# Octoprober.net
KiCad netlist of a schematic drawn in EAGLE
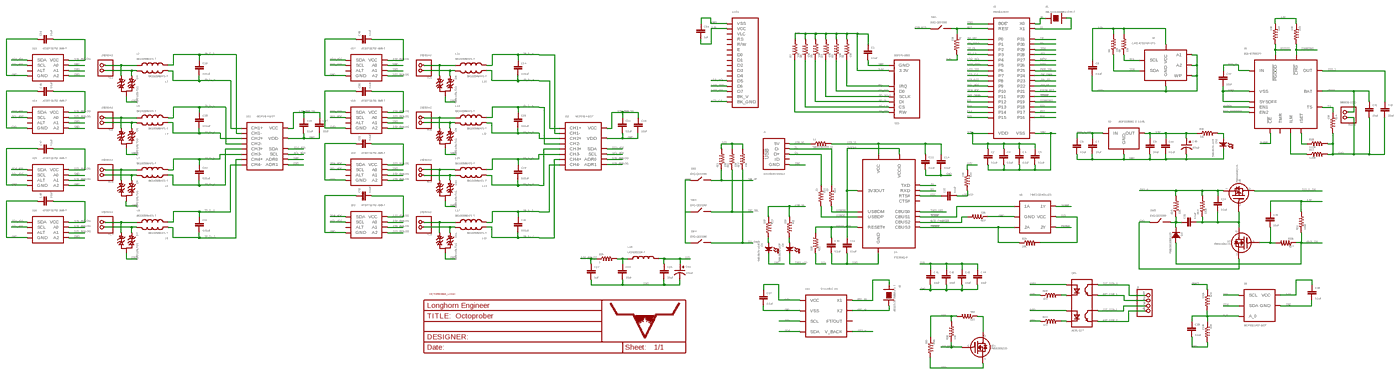
[diagram p0: schematic, sheet 1, overview]
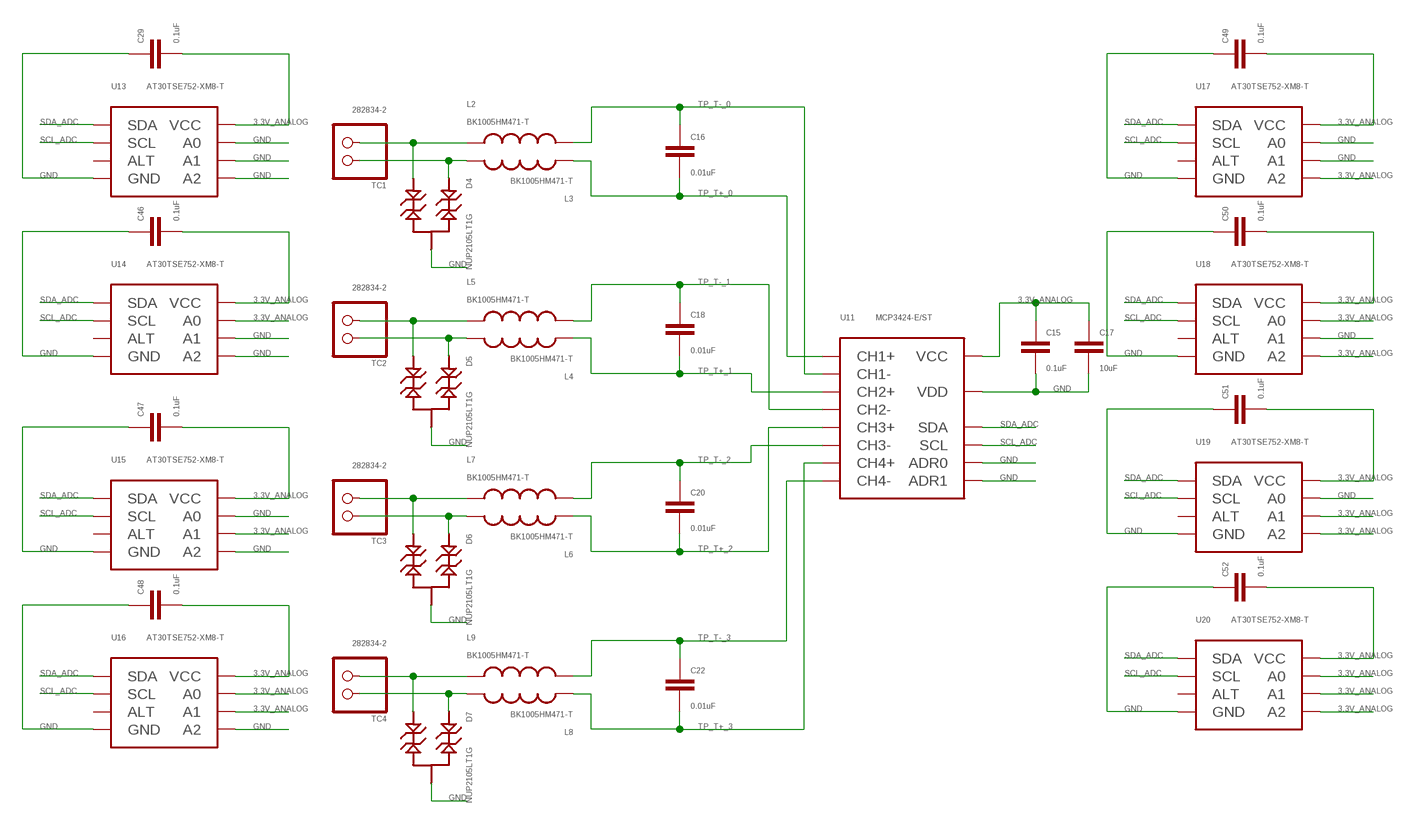
[diagram p1: schematic, sheet 1, part 1 of 4]
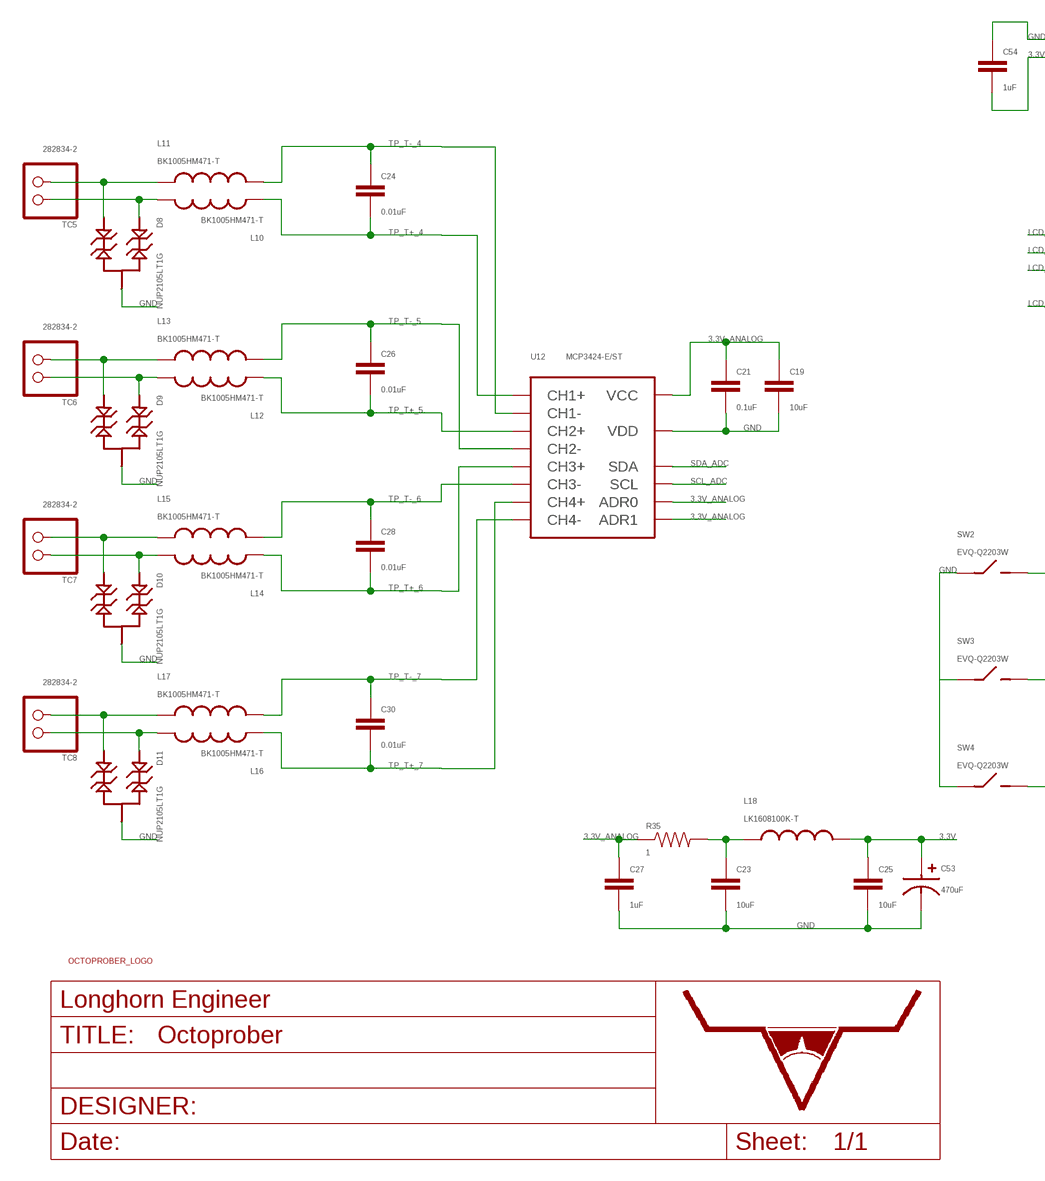
[diagram p2: schematic, sheet 1, part 2 of 4]
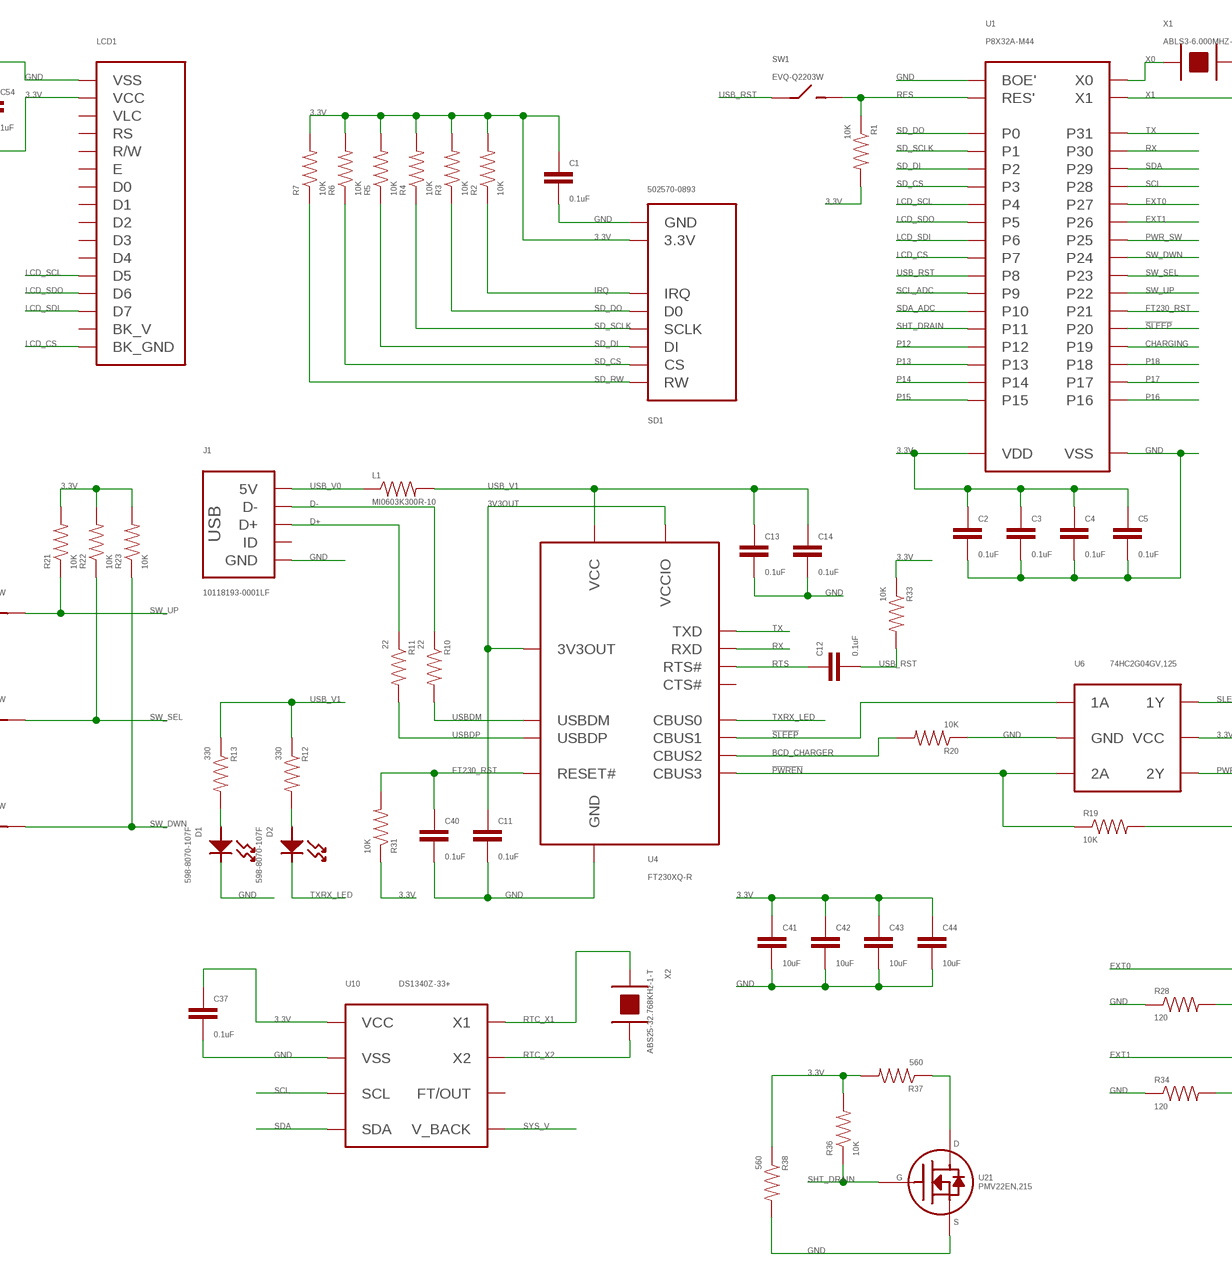
[diagram p3: schematic, sheet 1, part 3 of 4]
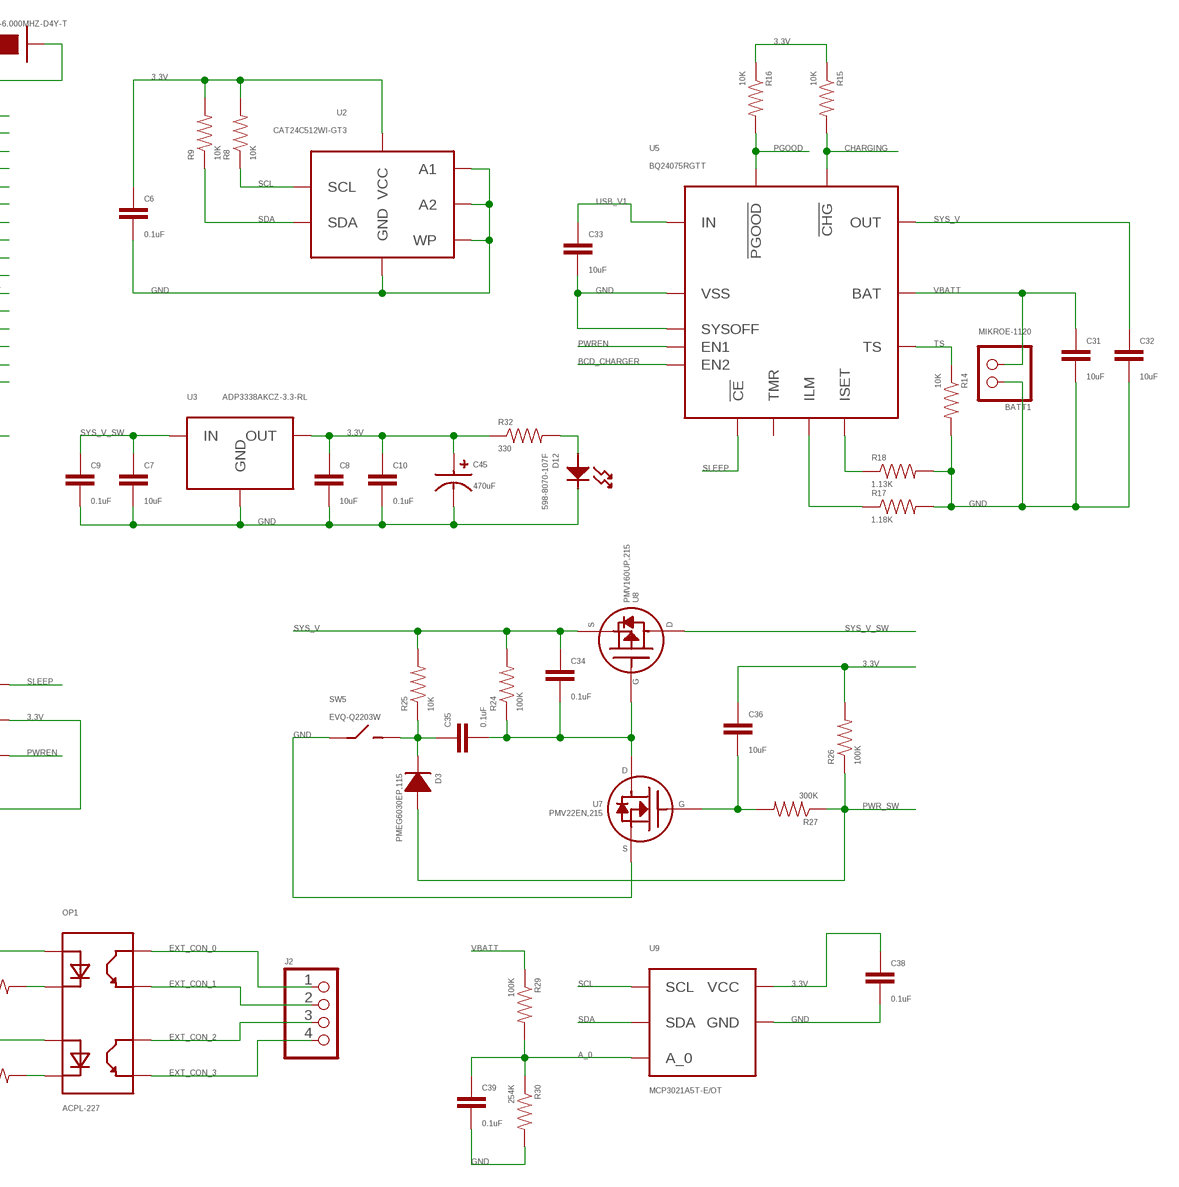
[diagram p4: schematic, sheet 1, part 4 of 4]

(export (version "E")
  (design (tool "Eeschema 10.0.6"))
  (components
    (comp (ref "BATT1")
      (value "MIKROE-1120")
      (footprint "eagle-import:HEADER_01X02_PTH")
      (libsource (lib "eagle-import") (part "PH_1X02HEADER_PTH"))
    )
    (comp (ref "C1")
      (value "0.1uF")
      (footprint "eagle-import:0402")
      (libsource (lib "eagle-import") (part "CAPACITOR_NON_POLAR0402"))
    )
    (comp (ref "C2")
      (value "0.1uF")
      (footprint "eagle-import:0402")
      (libsource (lib "eagle-import") (part "CAPACITOR_NON_POLAR0402"))
    )
    (comp (ref "C3")
      (value "0.1uF")
      (footprint "eagle-import:0402")
      (libsource (lib "eagle-import") (part "CAPACITOR_NON_POLAR0402"))
    )
    (comp (ref "C4")
      (value "0.1uF")
      (footprint "eagle-import:0402")
      (libsource (lib "eagle-import") (part "CAPACITOR_NON_POLAR0402"))
    )
    (comp (ref "C5")
      (value "0.1uF")
      (footprint "eagle-import:0402")
      (libsource (lib "eagle-import") (part "CAPACITOR_NON_POLAR0402"))
    )
    (comp (ref "C6")
      (value "0.1uF")
      (footprint "eagle-import:0402")
      (libsource (lib "eagle-import") (part "CAPACITOR_NON_POLAR0402"))
    )
    (comp (ref "C7")
      (value "10uF")
      (footprint "eagle-import:1206")
      (libsource (lib "eagle-import") (part "CAPACITOR_NON_POLAR1206"))
    )
    (comp (ref "C8")
      (value "10uF")
      (footprint "eagle-import:1206")
      (libsource (lib "eagle-import") (part "CAPACITOR_NON_POLAR1206"))
    )
    (comp (ref "C9")
      (value "0.1uF")
      (footprint "eagle-import:0402")
      (libsource (lib "eagle-import") (part "CAPACITOR_NON_POLAR0402"))
    )
    (comp (ref "C10")
      (value "0.1uF")
      (footprint "eagle-import:0402")
      (libsource (lib "eagle-import") (part "CAPACITOR_NON_POLAR0402"))
    )
    (comp (ref "C11")
      (value "0.1uF")
      (footprint "eagle-import:0402")
      (libsource (lib "eagle-import") (part "CAPACITOR_NON_POLAR0402"))
    )
    (comp (ref "C12")
      (value "0.1uF")
      (footprint "eagle-import:0402")
      (libsource (lib "eagle-import") (part "CAPACITOR_NON_POLAR0402"))
    )
    (comp (ref "C13")
      (value "0.1uF")
      (footprint "eagle-import:0402")
      (libsource (lib "eagle-import") (part "CAPACITOR_NON_POLAR0402"))
    )
    (comp (ref "C14")
      (value "0.1uF")
      (footprint "eagle-import:0402")
      (libsource (lib "eagle-import") (part "CAPACITOR_NON_POLAR0402"))
    )
    (comp (ref "C15")
      (value "0.1uF")
      (footprint "eagle-import:0402")
      (libsource (lib "eagle-import") (part "CAPACITOR_NON_POLAR0402"))
    )
    (comp (ref "C16")
      (value "0.01uF")
      (footprint "eagle-import:0402")
      (libsource (lib "eagle-import") (part "CAPACITOR_NON_POLAR0402"))
    )
    (comp (ref "C17")
      (value "10uF")
      (footprint "eagle-import:0402")
      (libsource (lib "eagle-import") (part "CAPACITOR_NON_POLAR0402"))
    )
    (comp (ref "C18")
      (value "0.01uF")
      (footprint "eagle-import:0402")
      (libsource (lib "eagle-import") (part "CAPACITOR_NON_POLAR0402"))
    )
    (comp (ref "C19")
      (value "10uF")
      (footprint "eagle-import:0402")
      (libsource (lib "eagle-import") (part "CAPACITOR_NON_POLAR0402"))
    )
    (comp (ref "C20")
      (value "0.01uF")
      (footprint "eagle-import:0402")
      (libsource (lib "eagle-import") (part "CAPACITOR_NON_POLAR0402"))
    )
    (comp (ref "C21")
      (value "0.1uF")
      (footprint "eagle-import:0402")
      (libsource (lib "eagle-import") (part "CAPACITOR_NON_POLAR0402"))
    )
    (comp (ref "C22")
      (value "0.01uF")
      (footprint "eagle-import:0402")
      (libsource (lib "eagle-import") (part "CAPACITOR_NON_POLAR0402"))
    )
    (comp (ref "C23")
      (value "10uF")
      (footprint "eagle-import:0402")
      (libsource (lib "eagle-import") (part "CAPACITOR_NON_POLAR0402"))
    )
    (comp (ref "C24")
      (value "0.01uF")
      (footprint "eagle-import:0402")
      (libsource (lib "eagle-import") (part "CAPACITOR_NON_POLAR0402"))
    )
    (comp (ref "C25")
      (value "10uF")
      (footprint "eagle-import:0402")
      (libsource (lib "eagle-import") (part "CAPACITOR_NON_POLAR0402"))
    )
    (comp (ref "C26")
      (value "0.01uF")
      (footprint "eagle-import:0402")
      (libsource (lib "eagle-import") (part "CAPACITOR_NON_POLAR0402"))
    )
    (comp (ref "C27")
      (value "1uF")
      (footprint "eagle-import:0402")
      (libsource (lib "eagle-import") (part "CAPACITOR_NON_POLAR0402"))
    )
    (comp (ref "C28")
      (value "0.01uF")
      (footprint "eagle-import:0402")
      (libsource (lib "eagle-import") (part "CAPACITOR_NON_POLAR0402"))
    )
    (comp (ref "C29")
      (value "0.1uF")
      (footprint "eagle-import:0402")
      (libsource (lib "eagle-import") (part "CAPACITOR_NON_POLAR0402"))
    )
    (comp (ref "C30")
      (value "0.01uF")
      (footprint "eagle-import:0402")
      (libsource (lib "eagle-import") (part "CAPACITOR_NON_POLAR0402"))
    )
    (comp (ref "C31")
      (value "10uF")
      (footprint "eagle-import:1206")
      (libsource (lib "eagle-import") (part "CAPACITOR_NON_POLAR1206"))
    )
    (comp (ref "C32")
      (value "10uF")
      (footprint "eagle-import:1206")
      (libsource (lib "eagle-import") (part "CAPACITOR_NON_POLAR1206"))
    )
    (comp (ref "C33")
      (value "10uF")
      (footprint "eagle-import:1206")
      (libsource (lib "eagle-import") (part "CAPACITOR_NON_POLAR1206"))
    )
    (comp (ref "C34")
      (value "0.1uF")
      (footprint "eagle-import:0402")
      (libsource (lib "eagle-import") (part "CAPACITOR_NON_POLAR0402"))
    )
    (comp (ref "C35")
      (value "0.1uF")
      (footprint "eagle-import:0402")
      (libsource (lib "eagle-import") (part "CAPACITOR_NON_POLAR0402"))
    )
    (comp (ref "C36")
      (value "10uF")
      (footprint "eagle-import:1206")
      (libsource (lib "eagle-import") (part "CAPACITOR_NON_POLAR1206"))
    )
    (comp (ref "C37")
      (value "0.1uF")
      (footprint "eagle-import:0402")
      (libsource (lib "eagle-import") (part "CAPACITOR_NON_POLAR0402"))
    )
    (comp (ref "C38")
      (value "0.1uF")
      (footprint "eagle-import:0402")
      (libsource (lib "eagle-import") (part "CAPACITOR_NON_POLAR0402"))
    )
    (comp (ref "C39")
      (value "0.1uF")
      (footprint "eagle-import:0402")
      (libsource (lib "eagle-import") (part "CAPACITOR_NON_POLAR0402"))
    )
    (comp (ref "C40")
      (value "0.1uF")
      (footprint "eagle-import:0402")
      (libsource (lib "eagle-import") (part "CAPACITOR_NON_POLAR0402"))
    )
    (comp (ref "C41")
      (value "10uF")
      (footprint "eagle-import:0402")
      (libsource (lib "eagle-import") (part "CAPACITOR_NON_POLAR0402"))
    )
    (comp (ref "C42")
      (value "10uF")
      (footprint "eagle-import:0402")
      (libsource (lib "eagle-import") (part "CAPACITOR_NON_POLAR0402"))
    )
    (comp (ref "C43")
      (value "10uF")
      (footprint "eagle-import:0402")
      (libsource (lib "eagle-import") (part "CAPACITOR_NON_POLAR0402"))
    )
    (comp (ref "C44")
      (value "10uF")
      (footprint "eagle-import:0402")
      (libsource (lib "eagle-import") (part "CAPACITOR_NON_POLAR0402"))
    )
    (comp (ref "C45")
      (value "470uF")
      (footprint "eagle-import:CASE_D")
      (libsource (lib "eagle-import") (part "CAPACITOR_POLARIZEDCASE_D"))
    )
    (comp (ref "C46")
      (value "0.1uF")
      (footprint "eagle-import:0402")
      (libsource (lib "eagle-import") (part "CAPACITOR_NON_POLAR0402"))
    )
    (comp (ref "C47")
      (value "0.1uF")
      (footprint "eagle-import:0402")
      (libsource (lib "eagle-import") (part "CAPACITOR_NON_POLAR0402"))
    )
    (comp (ref "C48")
      (value "0.1uF")
      (footprint "eagle-import:0402")
      (libsource (lib "eagle-import") (part "CAPACITOR_NON_POLAR0402"))
    )
    (comp (ref "C49")
      (value "0.1uF")
      (footprint "eagle-import:0402")
      (libsource (lib "eagle-import") (part "CAPACITOR_NON_POLAR0402"))
    )
    (comp (ref "C50")
      (value "0.1uF")
      (footprint "eagle-import:0402")
      (libsource (lib "eagle-import") (part "CAPACITOR_NON_POLAR0402"))
    )
    (comp (ref "C51")
      (value "0.1uF")
      (footprint "eagle-import:0402")
      (libsource (lib "eagle-import") (part "CAPACITOR_NON_POLAR0402"))
    )
    (comp (ref "C52")
      (value "0.1uF")
      (footprint "eagle-import:0402")
      (libsource (lib "eagle-import") (part "CAPACITOR_NON_POLAR0402"))
    )
    (comp (ref "C53")
      (value "470uF")
      (footprint "eagle-import:CASE_D")
      (libsource (lib "eagle-import") (part "CAPACITOR_POLARIZEDCASE_D"))
    )
    (comp (ref "C54")
      (value "1uF")
      (footprint "eagle-import:0402")
      (libsource (lib "eagle-import") (part "CAPACITOR_NON_POLAR0402"))
    )
    (comp (ref "D1")
      (value "598-8070-107F")
      (footprint "eagle-import:LED_0402")
      (libsource (lib "eagle-import") (part "LED_SINGLE0402"))
    )
    (comp (ref "D2")
      (value "598-8070-107F")
      (footprint "eagle-import:LED_0402")
      (libsource (lib "eagle-import") (part "LED_SINGLE0402"))
    )
    (comp (ref "D3")
      (value "PMEG6030EP,115")
      (footprint "eagle-import:SOD-128")
      (libsource (lib "eagle-import") (part "DIODESOD-128"))
    )
    (comp (ref "D4")
      (value "NUP2105LT1G")
      (footprint "eagle-import:SOT-23")
      (libsource (lib "eagle-import") (part "TVS_DIODE_DUALSOT-23"))
    )
    (comp (ref "D5")
      (value "NUP2105LT1G")
      (footprint "eagle-import:SOT-23")
      (libsource (lib "eagle-import") (part "TVS_DIODE_DUALSOT-23"))
    )
    (comp (ref "D6")
      (value "NUP2105LT1G")
      (footprint "eagle-import:SOT-23")
      (libsource (lib "eagle-import") (part "TVS_DIODE_DUALSOT-23"))
    )
    (comp (ref "D7")
      (value "NUP2105LT1G")
      (footprint "eagle-import:SOT-23")
      (libsource (lib "eagle-import") (part "TVS_DIODE_DUALSOT-23"))
    )
    (comp (ref "D8")
      (value "NUP2105LT1G")
      (footprint "eagle-import:SOT-23")
      (libsource (lib "eagle-import") (part "TVS_DIODE_DUALSOT-23"))
    )
    (comp (ref "D9")
      (value "NUP2105LT1G")
      (footprint "eagle-import:SOT-23")
      (libsource (lib "eagle-import") (part "TVS_DIODE_DUALSOT-23"))
    )
    (comp (ref "D10")
      (value "NUP2105LT1G")
      (footprint "eagle-import:SOT-23")
      (libsource (lib "eagle-import") (part "TVS_DIODE_DUALSOT-23"))
    )
    (comp (ref "D11")
      (value "NUP2105LT1G")
      (footprint "eagle-import:SOT-23")
      (libsource (lib "eagle-import") (part "TVS_DIODE_DUALSOT-23"))
    )
    (comp (ref "D12")
      (value "598-8070-107F")
      (footprint "eagle-import:LED_0402")
      (libsource (lib "eagle-import") (part "LED_SINGLE0402"))
    )
    (comp (ref "J1")
      (value "10118193-0001LF")
      (footprint "eagle-import:10118193-0001LF")
      (libsource (lib "eagle-import") (part "USB10118193-0001LF"))
    )
    (comp (ref "J2")
      (value "PH_1X04HEADER_PTH")
      (footprint "eagle-import:HEADER_01X04_PTH")
      (libsource (lib "eagle-import") (part "PH_1X04HEADER_PTH"))
    )
    (comp (ref "L1")
      (value "MI0603K300R-10")
      (footprint "eagle-import:0603")
      (libsource (lib "eagle-import") (part "RESISTOR0603"))
    )
    (comp (ref "L2")
      (value "BK1005HM471-T")
      (footprint "eagle-import:0402")
      (libsource (lib "eagle-import") (part "INDUCTOR0402"))
    )
    (comp (ref "L3")
      (value "BK1005HM471-T")
      (footprint "eagle-import:0402")
      (libsource (lib "eagle-import") (part "INDUCTOR0402"))
    )
    (comp (ref "L4")
      (value "BK1005HM471-T")
      (footprint "eagle-import:0402")
      (libsource (lib "eagle-import") (part "INDUCTOR0402"))
    )
    (comp (ref "L5")
      (value "BK1005HM471-T")
      (footprint "eagle-import:0402")
      (libsource (lib "eagle-import") (part "INDUCTOR0402"))
    )
    (comp (ref "L6")
      (value "BK1005HM471-T")
      (footprint "eagle-import:0402")
      (libsource (lib "eagle-import") (part "INDUCTOR0402"))
    )
    (comp (ref "L7")
      (value "BK1005HM471-T")
      (footprint "eagle-import:0402")
      (libsource (lib "eagle-import") (part "INDUCTOR0402"))
    )
    (comp (ref "L8")
      (value "BK1005HM471-T")
      (footprint "eagle-import:0402")
      (libsource (lib "eagle-import") (part "INDUCTOR0402"))
    )
    (comp (ref "L9")
      (value "BK1005HM471-T")
      (footprint "eagle-import:0402")
      (libsource (lib "eagle-import") (part "INDUCTOR0402"))
    )
    (comp (ref "L10")
      (value "BK1005HM471-T")
      (footprint "eagle-import:0402")
      (libsource (lib "eagle-import") (part "INDUCTOR0402"))
    )
    (comp (ref "L11")
      (value "BK1005HM471-T")
      (footprint "eagle-import:0402")
      (libsource (lib "eagle-import") (part "INDUCTOR0402"))
    )
    (comp (ref "L12")
      (value "BK1005HM471-T")
      (footprint "eagle-import:0402")
      (libsource (lib "eagle-import") (part "INDUCTOR0402"))
    )
    (comp (ref "L13")
      (value "BK1005HM471-T")
      (footprint "eagle-import:0402")
      (libsource (lib "eagle-import") (part "INDUCTOR0402"))
    )
    (comp (ref "L14")
      (value "BK1005HM471-T")
      (footprint "eagle-import:0402")
      (libsource (lib "eagle-import") (part "INDUCTOR0402"))
    )
    (comp (ref "L15")
      (value "BK1005HM471-T")
      (footprint "eagle-import:0402")
      (libsource (lib "eagle-import") (part "INDUCTOR0402"))
    )
    (comp (ref "L16")
      (value "BK1005HM471-T")
      (footprint "eagle-import:0402")
      (libsource (lib "eagle-import") (part "INDUCTOR0402"))
    )
    (comp (ref "L17")
      (value "BK1005HM471-T")
      (footprint "eagle-import:0402")
      (libsource (lib "eagle-import") (part "INDUCTOR0402"))
    )
    (comp (ref "L18")
      (value "LK1608100K-T")
      (footprint "eagle-import:0603")
      (libsource (lib "eagle-import") (part "INDUCTOR0603"))
    )
    (comp (ref "LCD1")
      (value "HD44780_LCD1602_COUNTERSINK")
      (footprint "eagle-import:CHAR_DISPLAY_1602_COUNTERSINK")
      (libsource (lib "eagle-import") (part "HD44780_LCD1602_COUNTERSINK"))
    )
    (comp (ref "OP1")
      (value "ACPL-227")
      (footprint "eagle-import:SOIC-8")
      (libsource (lib "eagle-import") (part "ACPL-227SOIC-8"))
    )
    (comp (ref "R1")
      (value "10K")
      (footprint "eagle-import:0402")
      (libsource (lib "eagle-import") (part "RESISTOR0402"))
    )
    (comp (ref "R2")
      (value "10K")
      (footprint "eagle-import:0402")
      (libsource (lib "eagle-import") (part "RESISTOR0402"))
    )
    (comp (ref "R3")
      (value "10K")
      (footprint "eagle-import:0402")
      (libsource (lib "eagle-import") (part "RESISTOR0402"))
    )
    (comp (ref "R4")
      (value "10K")
      (footprint "eagle-import:0402")
      (libsource (lib "eagle-import") (part "RESISTOR0402"))
    )
    (comp (ref "R5")
      (value "10K")
      (footprint "eagle-import:0402")
      (libsource (lib "eagle-import") (part "RESISTOR0402"))
    )
    (comp (ref "R6")
      (value "10K")
      (footprint "eagle-import:0402")
      (libsource (lib "eagle-import") (part "RESISTOR0402"))
    )
    (comp (ref "R7")
      (value "10K")
      (footprint "eagle-import:0402")
      (libsource (lib "eagle-import") (part "RESISTOR0402"))
    )
    (comp (ref "R8")
      (value "10K")
      (footprint "eagle-import:0402")
      (libsource (lib "eagle-import") (part "RESISTOR0402"))
    )
    (comp (ref "R9")
      (value "10K")
      (footprint "eagle-import:0402")
      (libsource (lib "eagle-import") (part "RESISTOR0402"))
    )
    (comp (ref "R10")
      (value "22")
      (footprint "eagle-import:0402")
      (libsource (lib "eagle-import") (part "RESISTOR0402"))
    )
    (comp (ref "R11")
      (value "22")
      (footprint "eagle-import:0402")
      (libsource (lib "eagle-import") (part "RESISTOR0402"))
    )
    (comp (ref "R12")
      (value "330")
      (footprint "eagle-import:0402")
      (libsource (lib "eagle-import") (part "RESISTOR0402"))
    )
    (comp (ref "R13")
      (value "330")
      (footprint "eagle-import:0402")
      (libsource (lib "eagle-import") (part "RESISTOR0402"))
    )
    (comp (ref "R14")
      (value "10K")
      (footprint "eagle-import:0402")
      (libsource (lib "eagle-import") (part "RESISTOR0402"))
    )
    (comp (ref "R15")
      (value "10K")
      (footprint "eagle-import:0402")
      (libsource (lib "eagle-import") (part "RESISTOR0402"))
    )
    (comp (ref "R16")
      (value "10K")
      (footprint "eagle-import:0402")
      (libsource (lib "eagle-import") (part "RESISTOR0402"))
    )
    (comp (ref "R17")
      (value "1.18K")
      (footprint "eagle-import:0402")
      (libsource (lib "eagle-import") (part "RESISTOR0402"))
    )
    (comp (ref "R18")
      (value "1.13K")
      (footprint "eagle-import:0402")
      (libsource (lib "eagle-import") (part "RESISTOR0402"))
    )
    (comp (ref "R19")
      (value "10K")
      (footprint "eagle-import:0402")
      (libsource (lib "eagle-import") (part "RESISTOR0402"))
    )
    (comp (ref "R20")
      (value "10K")
      (footprint "eagle-import:0402")
      (libsource (lib "eagle-import") (part "RESISTOR0402"))
    )
    (comp (ref "R21")
      (value "10K")
      (footprint "eagle-import:0402")
      (libsource (lib "eagle-import") (part "RESISTOR0402"))
    )
    (comp (ref "R22")
      (value "10K")
      (footprint "eagle-import:0402")
      (libsource (lib "eagle-import") (part "RESISTOR0402"))
    )
    (comp (ref "R23")
      (value "10K")
      (footprint "eagle-import:0402")
      (libsource (lib "eagle-import") (part "RESISTOR0402"))
    )
    (comp (ref "R24")
      (value "100K")
      (footprint "eagle-import:0402")
      (libsource (lib "eagle-import") (part "RESISTOR0402"))
    )
    (comp (ref "R25")
      (value "10K")
      (footprint "eagle-import:0402")
      (libsource (lib "eagle-import") (part "RESISTOR0402"))
    )
    (comp (ref "R26")
      (value "100K")
      (footprint "eagle-import:0402")
      (libsource (lib "eagle-import") (part "RESISTOR0402"))
    )
    (comp (ref "R27")
      (value "300K")
      (footprint "eagle-import:0402")
      (libsource (lib "eagle-import") (part "RESISTOR0402"))
    )
    (comp (ref "R28")
      (value "120")
      (footprint "eagle-import:0402")
      (libsource (lib "eagle-import") (part "RESISTOR0402"))
    )
    (comp (ref "R29")
      (value "100K")
      (footprint "eagle-import:0402")
      (libsource (lib "eagle-import") (part "RESISTOR0402"))
    )
    (comp (ref "R30")
      (value "254K")
      (footprint "eagle-import:0402")
      (libsource (lib "eagle-import") (part "RESISTOR0402"))
    )
    (comp (ref "R31")
      (value "10K")
      (footprint "eagle-import:0402")
      (libsource (lib "eagle-import") (part "RESISTOR0402"))
    )
    (comp (ref "R32")
      (value "330")
      (footprint "eagle-import:0402")
      (libsource (lib "eagle-import") (part "RESISTOR0402"))
    )
    (comp (ref "R33")
      (value "10K")
      (footprint "eagle-import:0402")
      (libsource (lib "eagle-import") (part "RESISTOR0402"))
    )
    (comp (ref "R34")
      (value "120")
      (footprint "eagle-import:0402")
      (libsource (lib "eagle-import") (part "RESISTOR0402"))
    )
    (comp (ref "R35")
      (value "1")
      (footprint "eagle-import:0402")
      (libsource (lib "eagle-import") (part "RESISTOR0402"))
    )
    (comp (ref "R36")
      (value "10K")
      (footprint "eagle-import:0402")
      (libsource (lib "eagle-import") (part "RESISTOR0402"))
    )
    (comp (ref "R37")
      (value "560")
      (footprint "eagle-import:0402")
      (libsource (lib "eagle-import") (part "RESISTOR0402"))
    )
    (comp (ref "R38")
      (value "560")
      (footprint "eagle-import:0402")
      (libsource (lib "eagle-import") (part "RESISTOR0402"))
    )
    (comp (ref "SD1")
      (value "502570-0893")
      (footprint "eagle-import:502570-0893")
      (libsource (lib "eagle-import") (part "SD_CARD502570-0893"))
    )
    (comp (ref "SW1")
      (value "EVQ-Q2203W")
      (footprint "eagle-import:EVQ-Q2203W")
      (libsource (lib "eagle-import") (part "SPSTEVQ-Q2203W"))
    )
    (comp (ref "SW2")
      (value "EVQ-Q2203W")
      (footprint "eagle-import:EVQ-Q2203W")
      (libsource (lib "eagle-import") (part "SPSTEVQ-Q2203W"))
    )
    (comp (ref "SW3")
      (value "EVQ-Q2203W")
      (footprint "eagle-import:EVQ-Q2203W")
      (libsource (lib "eagle-import") (part "SPSTEVQ-Q2203W"))
    )
    (comp (ref "SW4")
      (value "EVQ-Q2203W")
      (footprint "eagle-import:EVQ-Q2203W")
      (libsource (lib "eagle-import") (part "SPSTEVQ-Q2203W"))
    )
    (comp (ref "SW5")
      (value "EVQ-Q2203W")
      (footprint "eagle-import:EVQ-Q2203W")
      (libsource (lib "eagle-import") (part "SPSTEVQ-Q2203W"))
    )
    (comp (ref "TC1")
      (value "282834-2")
      (footprint "eagle-import:HEADER_01X02_PTH_SCREWTERM")
      (libsource (lib "eagle-import") (part "PH_1X02SCREW_TERM"))
    )
    (comp (ref "TC2")
      (value "282834-2")
      (footprint "eagle-import:HEADER_01X02_PTH_SCREWTERM")
      (libsource (lib "eagle-import") (part "PH_1X02SCREW_TERM"))
    )
    (comp (ref "TC3")
      (value "282834-2")
      (footprint "eagle-import:HEADER_01X02_PTH_SCREWTERM")
      (libsource (lib "eagle-import") (part "PH_1X02SCREW_TERM"))
    )
    (comp (ref "TC4")
      (value "282834-2")
      (footprint "eagle-import:HEADER_01X02_PTH_SCREWTERM")
      (libsource (lib "eagle-import") (part "PH_1X02SCREW_TERM"))
    )
    (comp (ref "TC5")
      (value "282834-2")
      (footprint "eagle-import:HEADER_01X02_PTH_SCREWTERM")
      (libsource (lib "eagle-import") (part "PH_1X02SCREW_TERM"))
    )
    (comp (ref "TC6")
      (value "282834-2")
      (footprint "eagle-import:HEADER_01X02_PTH_SCREWTERM")
      (libsource (lib "eagle-import") (part "PH_1X02SCREW_TERM"))
    )
    (comp (ref "TC7")
      (value "282834-2")
      (footprint "eagle-import:HEADER_01X02_PTH_SCREWTERM")
      (libsource (lib "eagle-import") (part "PH_1X02SCREW_TERM"))
    )
    (comp (ref "TC8")
      (value "282834-2")
      (footprint "eagle-import:HEADER_01X02_PTH_SCREWTERM")
      (libsource (lib "eagle-import") (part "PH_1X02SCREW_TERM"))
    )
    (comp (ref "U$1")
      (value "LHE_FRAME")
      (footprint "eagle-import:LHE_FRAME")
      (fields (field (name "DNAME") "Parker Dillmann") (field (name "REVNUM") "REV 2"))
      (libsource (lib "eagle-import") (part "LHE_FRAME"))
    )
    (comp (ref "U$2")
      (value "OCTOPROBER_LOGONORMAL")
      (footprint "eagle-import:OCTOPROBER_LOGO")
      (libsource (lib "eagle-import") (part "OCTOPROBER_LOGONORMAL"))
    )
    (comp (ref "U1")
      (value "P8X32A-M44")
      (footprint "eagle-import:QFN-44")
      (libsource (lib "eagle-import") (part "P8X32A_PROPELLERQFN-44"))
    )
    (comp (ref "U2")
      (value "CAT24C512WI-GT3")
      (footprint "eagle-import:SOIC-8_W")
      (libsource (lib "eagle-import") (part "CAT24M01XI-T2SOIC-8_W"))
    )
    (comp (ref "U3")
      (value "ADP3338AKCZ-3.3-RL")
      (footprint "eagle-import:SOT-223")
      (libsource (lib "eagle-import") (part "FIXED_VOLTAGE_REGSOT-223_ALT"))
    )
    (comp (ref "U4")
      (value "FT230XQ-R")
      (footprint "eagle-import:QFN-16")
      (libsource (lib "eagle-import") (part "FT230XQFN-16"))
    )
    (comp (ref "U5")
      (value "BQ24075RGTT")
      (footprint "eagle-import:QFN-16_BOT_PAD")
      (libsource (lib "eagle-import") (part "BQ2407XQFN-16"))
    )
    (comp (ref "U6")
      (value "74HC2G04GV,125")
      (footprint "eagle-import:TTSOP-6")
      (libsource (lib "eagle-import") (part "74HCT2G04GV,125TTSOP-6"))
    )
    (comp (ref "U7")
      (value "PMV22EN,215")
      (footprint "eagle-import:SOT-23")
      (libsource (lib "eagle-import") (part "MOSFET_N-CHANNEL_SINGLESOT-23"))
    )
    (comp (ref "U8")
      (value "PMV160UP,215")
      (footprint "eagle-import:SOT-23")
      (libsource (lib "eagle-import") (part "MOSFET_P-CHANNEL_SINGLESOT-23"))
    )
    (comp (ref "U9")
      (value "MCP3021A5T-E/OT")
      (footprint "eagle-import:SOT-23A")
      (libsource (lib "eagle-import") (part "MCP3021SOT-23A"))
    )
    (comp (ref "U10")
      (value "DS1340Z-33+")
      (footprint "eagle-import:SOIC-8")
      (libsource (lib "eagle-import") (part "DS1340SOIC-8"))
    )
    (comp (ref "U11")
      (value "MCP3424-E/ST")
      (footprint "eagle-import:TTSOP-14")
      (libsource (lib "eagle-import") (part "MCP3424TTSOP-14"))
    )
    (comp (ref "U12")
      (value "MCP3424-E/ST")
      (footprint "eagle-import:TTSOP-14")
      (libsource (lib "eagle-import") (part "MCP3424TTSOP-14"))
    )
    (comp (ref "U13")
      (value "AT30TSE752-XM8-T")
      (footprint "eagle-import:MSOP-8")
      (libsource (lib "eagle-import") (part "AT30TSEXXXMSOP-8"))
    )
    (comp (ref "U14")
      (value "AT30TSE752-XM8-T")
      (footprint "eagle-import:MSOP-8")
      (libsource (lib "eagle-import") (part "AT30TSEXXXMSOP-8"))
    )
    (comp (ref "U15")
      (value "AT30TSE752-XM8-T")
      (footprint "eagle-import:MSOP-8")
      (libsource (lib "eagle-import") (part "AT30TSEXXXMSOP-8"))
    )
    (comp (ref "U16")
      (value "AT30TSE752-XM8-T")
      (footprint "eagle-import:MSOP-8")
      (libsource (lib "eagle-import") (part "AT30TSEXXXMSOP-8"))
    )
    (comp (ref "U17")
      (value "AT30TSE752-XM8-T")
      (footprint "eagle-import:MSOP-8")
      (libsource (lib "eagle-import") (part "AT30TSEXXXMSOP-8"))
    )
    (comp (ref "U18")
      (value "AT30TSE752-XM8-T")
      (footprint "eagle-import:MSOP-8")
      (libsource (lib "eagle-import") (part "AT30TSEXXXMSOP-8"))
    )
    (comp (ref "U19")
      (value "AT30TSE752-XM8-T")
      (footprint "eagle-import:MSOP-8")
      (libsource (lib "eagle-import") (part "AT30TSEXXXMSOP-8"))
    )
    (comp (ref "U20")
      (value "AT30TSE752-XM8-T")
      (footprint "eagle-import:MSOP-8")
      (libsource (lib "eagle-import") (part "AT30TSEXXXMSOP-8"))
    )
    (comp (ref "U21")
      (value "PMV22EN,215")
      (footprint "eagle-import:SOT-23")
      (libsource (lib "eagle-import") (part "MOSFET_N-CHANNEL_SINGLESOT-23"))
    )
    (comp (ref "X1")
      (value "ABLS3-6.000MHZ-D4Y-T")
      (footprint "eagle-import:HC-49_US_SM")
      (libsource (lib "eagle-import") (part "CRYSTALHC-49"))
    )
    (comp (ref "X2")
      (value "ABS25-32.768KHz-1-T")
      (footprint "eagle-import:8MM_X_3.8MM")
      (libsource (lib "eagle-import") (part "CRYSTAL8MM_X_3.8MM"))
    )
  )
  (nets
    (net (code "1") (name "/3.3V") (class "Default")
      (node (ref "C1") (pin "1") (pinfunction "1_1") (pintype "passive"))
      (node (ref "C10") (pin "1") (pinfunction "1_1") (pintype "passive"))
      (node (ref "C2") (pin "1") (pinfunction "1_1") (pintype "passive"))
      (node (ref "C25") (pin "1") (pinfunction "1_1") (pintype "passive"))
      (node (ref "C3") (pin "1") (pinfunction "1_1") (pintype "passive"))
      (node (ref "C36") (pin "1") (pinfunction "1_1") (pintype "passive"))
      (node (ref "C37") (pin "1") (pinfunction "1_1") (pintype "passive"))
      (node (ref "C38") (pin "1") (pinfunction "1_1") (pintype "passive"))
      (node (ref "C4") (pin "1") (pinfunction "1_1") (pintype "passive"))
      (node (ref "C41") (pin "1") (pinfunction "1_1") (pintype "passive"))
      (node (ref "C42") (pin "1") (pinfunction "1_1") (pintype "passive"))
      (node (ref "C43") (pin "1") (pinfunction "1_1") (pintype "passive"))
      (node (ref "C44") (pin "1") (pinfunction "1_1") (pintype "passive"))
      (node (ref "C45") (pin "P") (pinfunction "POS_P") (pintype "bidirectional"))
      (node (ref "C5") (pin "1") (pinfunction "1_1") (pintype "passive"))
      (node (ref "C53") (pin "P") (pinfunction "POS_P") (pintype "bidirectional"))
      (node (ref "C54") (pin "2") (pinfunction "2_2") (pintype "passive"))
      (node (ref "C6") (pin "1") (pinfunction "1_1") (pintype "passive"))
      (node (ref "C8") (pin "1") (pinfunction "1_1") (pintype "passive"))
      (node (ref "L18") (pin "2") (pinfunction "P$2_2") (pintype "bidirectional"))
      (node (ref "LCD1") (pin "2") (pinfunction "VCC_2") (pintype "bidirectional"))
      (node (ref "R1") (pin "2") (pinfunction "2_2") (pintype "passive"))
      (node (ref "R15") (pin "1") (pinfunction "1_1") (pintype "passive"))
      (node (ref "R16") (pin "1") (pinfunction "1_1") (pintype "passive"))
      (node (ref "R19") (pin "2") (pinfunction "2_2") (pintype "passive"))
      (node (ref "R2") (pin "2") (pinfunction "2_2") (pintype "passive"))
      (node (ref "R21") (pin "2") (pinfunction "2_2") (pintype "passive"))
      (node (ref "R22") (pin "2") (pinfunction "2_2") (pintype "passive"))
      (node (ref "R23") (pin "2") (pinfunction "2_2") (pintype "passive"))
      (node (ref "R26") (pin "2") (pinfunction "2_2") (pintype "passive"))
      (node (ref "R3") (pin "2") (pinfunction "2_2") (pintype "passive"))
      (node (ref "R31") (pin "1") (pinfunction "1_1") (pintype "passive"))
      (node (ref "R32") (pin "1") (pinfunction "1_1") (pintype "passive"))
      (node (ref "R33") (pin "1") (pinfunction "1_1") (pintype "passive"))
      (node (ref "R36") (pin "2") (pinfunction "2_2") (pintype "passive"))
      (node (ref "R37") (pin "2") (pinfunction "2_2") (pintype "passive"))
      (node (ref "R38") (pin "1") (pinfunction "1_1") (pintype "passive"))
      (node (ref "R4") (pin "2") (pinfunction "2_2") (pintype "passive"))
      (node (ref "R5") (pin "2") (pinfunction "2_2") (pintype "passive"))
      (node (ref "R6") (pin "2") (pinfunction "2_2") (pintype "passive"))
      (node (ref "R7") (pin "2") (pinfunction "2_2") (pintype "passive"))
      (node (ref "R8") (pin "2") (pinfunction "2_2") (pintype "passive"))
      (node (ref "R9") (pin "2") (pinfunction "2_2") (pintype "passive"))
      (node (ref "SD1") (pin "5") (pinfunction "3.3V_5") (pintype "bidirectional"))
      (node (ref "U1") (pin "18") (pinfunction "VDD_18") (pintype "bidirectional"))
      (node (ref "U1") (pin "30") (pinfunction "VDD_30") (pintype "bidirectional"))
      (node (ref "U1") (pin "40") (pinfunction "VDD_40") (pintype "bidirectional"))
      (node (ref "U1") (pin "8") (pinfunction "VDD_8") (pintype "bidirectional"))
      (node (ref "U10") (pin "8") (pinfunction "VCC_8") (pintype "bidirectional"))
      (node (ref "U2") (pin "8") (pinfunction "VCC_8") (pintype "bidirectional"))
      (node (ref "U3") (pin "COM1") (pinfunction "OUT_COM1") (pintype "bidirectional"))
      (node (ref "U3") (pin "COM2") (pinfunction "OUT_COM2") (pintype "bidirectional"))
      (node (ref "U6") (pin "5") (pinfunction "VCC_5") (pintype "bidirectional"))
      (node (ref "U9") (pin "1") (pinfunction "VCC_1") (pintype "bidirectional"))
    )
    (net (code "2") (name "/3.3V_ANALOG") (class "Default")
      (node (ref "C15") (pin "1") (pinfunction "1_1") (pintype "passive"))
      (node (ref "C17") (pin "1") (pinfunction "1_1") (pintype "passive"))
      (node (ref "C19") (pin "1") (pinfunction "1_1") (pintype "passive"))
      (node (ref "C21") (pin "1") (pinfunction "1_1") (pintype "passive"))
      (node (ref "C27") (pin "1") (pinfunction "1_1") (pintype "passive"))
      (node (ref "C29") (pin "2") (pinfunction "2_2") (pintype "passive"))
      (node (ref "C46") (pin "2") (pinfunction "2_2") (pintype "passive"))
      (node (ref "C47") (pin "2") (pinfunction "2_2") (pintype "passive"))
      (node (ref "C48") (pin "2") (pinfunction "2_2") (pintype "passive"))
      (node (ref "C49") (pin "2") (pinfunction "2_2") (pintype "passive"))
      (node (ref "C50") (pin "2") (pinfunction "2_2") (pintype "passive"))
      (node (ref "C51") (pin "2") (pinfunction "2_2") (pintype "passive"))
      (node (ref "C52") (pin "2") (pinfunction "2_2") (pintype "passive"))
      (node (ref "R35") (pin "1") (pinfunction "1_1") (pintype "passive"))
      (node (ref "U11") (pin "5") (pinfunction "VCC_5") (pintype "bidirectional"))
      (node (ref "U12") (pin "10") (pinfunction "ADR1_10") (pintype "bidirectional"))
      (node (ref "U12") (pin "5") (pinfunction "VCC_5") (pintype "bidirectional"))
      (node (ref "U12") (pin "9") (pinfunction "ADR0_9") (pintype "bidirectional"))
      (node (ref "U13") (pin "P$8") (pinfunction "VCC_P$8") (pintype "bidirectional"))
      (node (ref "U14") (pin "P$7") (pinfunction "A0_P$7") (pintype "bidirectional"))
      (node (ref "U14") (pin "P$8") (pinfunction "VCC_P$8") (pintype "bidirectional"))
      (node (ref "U15") (pin "P$6") (pinfunction "A1_P$6") (pintype "bidirectional"))
      (node (ref "U15") (pin "P$8") (pinfunction "VCC_P$8") (pintype "bidirectional"))
      (node (ref "U16") (pin "P$6") (pinfunction "A1_P$6") (pintype "bidirectional"))
      (node (ref "U16") (pin "P$7") (pinfunction "A0_P$7") (pintype "bidirectional"))
      (node (ref "U16") (pin "P$8") (pinfunction "VCC_P$8") (pintype "bidirectional"))
      (node (ref "U17") (pin "P$5") (pinfunction "A2_P$5") (pintype "bidirectional"))
      (node (ref "U17") (pin "P$8") (pinfunction "VCC_P$8") (pintype "bidirectional"))
      (node (ref "U18") (pin "P$5") (pinfunction "A2_P$5") (pintype "bidirectional"))
      (node (ref "U18") (pin "P$7") (pinfunction "A0_P$7") (pintype "bidirectional"))
      (node (ref "U18") (pin "P$8") (pinfunction "VCC_P$8") (pintype "bidirectional"))
      (node (ref "U19") (pin "P$5") (pinfunction "A2_P$5") (pintype "bidirectional"))
      (node (ref "U19") (pin "P$6") (pinfunction "A1_P$6") (pintype "bidirectional"))
      (node (ref "U19") (pin "P$8") (pinfunction "VCC_P$8") (pintype "bidirectional"))
      (node (ref "U20") (pin "P$5") (pinfunction "A2_P$5") (pintype "bidirectional"))
      (node (ref "U20") (pin "P$6") (pinfunction "A1_P$6") (pintype "bidirectional"))
      (node (ref "U20") (pin "P$7") (pinfunction "A0_P$7") (pintype "bidirectional"))
      (node (ref "U20") (pin "P$8") (pinfunction "VCC_P$8") (pintype "bidirectional"))
    )
    (net (code "3") (name "/3V3OUT") (class "Default")
      (node (ref "C11") (pin "1") (pinfunction "1_1") (pintype "passive"))
      (node (ref "U4") (pin "1") (pinfunction "VCCIO_1") (pintype "bidirectional"))
      (node (ref "U4") (pin "8") (pinfunction "3V3OUT_8") (pintype "bidirectional"))
    )
    (net (code "4") (name "/A_0") (class "Default")
      (node (ref "C39") (pin "1") (pinfunction "1_1") (pintype "passive"))
      (node (ref "R29") (pin "2") (pinfunction "2_2") (pintype "passive"))
      (node (ref "R30") (pin "1") (pinfunction "1_1") (pintype "passive"))
      (node (ref "U9") (pin "3") (pinfunction "A_0_3") (pintype "bidirectional"))
    )
    (net (code "5") (name "/BCD_CHARGER") (class "Default")
      (node (ref "R20") (pin "2") (pinfunction "2_2") (pintype "passive"))
      (node (ref "U4") (pin "5") (pinfunction "CBUS2_5") (pintype "bidirectional"))
      (node (ref "U5") (pin "5") (pinfunction "EN2_5") (pintype "bidirectional"))
    )
    (net (code "6") (name "/CHARGING") (class "Default")
      (node (ref "R15") (pin "2") (pinfunction "2_2") (pintype "passive"))
      (node (ref "U1") (pin "22") (pinfunction "P19_22") (pintype "bidirectional"))
      (node (ref "U5") (pin "9") (pinfunction "~{CHG}_9") (pintype "bidirectional"))
    )
    (net (code "7") (name "/D+") (class "Default")
      (node (ref "J1") (pin "3") (pinfunction "D+_3") (pintype "bidirectional"))
      (node (ref "R11") (pin "1") (pinfunction "1_1") (pintype "passive"))
    )
    (net (code "8") (name "/D-") (class "Default")
      (node (ref "J1") (pin "2") (pinfunction "D-_2") (pintype "bidirectional"))
      (node (ref "R10") (pin "1") (pinfunction "1_1") (pintype "passive"))
    )
    (net (code "9") (name "/EXT0") (class "Default")
      (node (ref "OP1") (pin "1") (pinfunction "1_1") (pintype "bidirectional"))
      (node (ref "U1") (pin "34") (pinfunction "P27_34") (pintype "bidirectional"))
    )
    (net (code "10") (name "/EXT1") (class "Default")
      (node (ref "OP1") (pin "3") (pinfunction "3_3") (pintype "bidirectional"))
      (node (ref "U1") (pin "33") (pinfunction "P26_33") (pintype "bidirectional"))
    )
    (net (code "11") (name "/EXT_CON_0") (class "Default")
      (node (ref "J2") (pin "1") (pinfunction "1_1") (pintype "passive"))
      (node (ref "OP1") (pin "8") (pinfunction "8_8") (pintype "bidirectional"))
    )
    (net (code "12") (name "/EXT_CON_1") (class "Default")
      (node (ref "J2") (pin "2") (pinfunction "2_2") (pintype "passive"))
      (node (ref "OP1") (pin "7") (pinfunction "7_7") (pintype "bidirectional"))
    )
    (net (code "13") (name "/EXT_CON_2") (class "Default")
      (node (ref "J2") (pin "3") (pinfunction "3_3") (pintype "passive"))
      (node (ref "OP1") (pin "6") (pinfunction "6_6") (pintype "bidirectional"))
    )
    (net (code "14") (name "/EXT_CON_3") (class "Default")
      (node (ref "J2") (pin "4") (pinfunction "4_4") (pintype "passive"))
      (node (ref "OP1") (pin "5") (pinfunction "5_5") (pintype "bidirectional"))
    )
    (net (code "15") (name "/FT230_RST") (class "Default")
      (node (ref "C40") (pin "1") (pinfunction "1_1") (pintype "passive"))
      (node (ref "R31") (pin "2") (pinfunction "2_2") (pintype "passive"))
      (node (ref "U1") (pin "24") (pinfunction "P21_24") (pintype "bidirectional"))
      (node (ref "U4") (pin "9") (pinfunction "RESET#_9") (pintype "bidirectional"))
    )
    (net (code "16") (name "/GND") (class "Default")
      (node (ref "BATT1") (pin "1") (pinfunction "1_1") (pintype "passive"))
      (node (ref "C1") (pin "2") (pinfunction "2_2") (pintype "passive"))
      (node (ref "C10") (pin "2") (pinfunction "2_2") (pintype "passive"))
      (node (ref "C11") (pin "2") (pinfunction "2_2") (pintype "passive"))
      (node (ref "C13") (pin "2") (pinfunction "2_2") (pintype "passive"))
      (node (ref "C14") (pin "2") (pinfunction "2_2") (pintype "passive"))
      (node (ref "C15") (pin "2") (pinfunction "2_2") (pintype "passive"))
      (node (ref "C17") (pin "2") (pinfunction "2_2") (pintype "passive"))
      (node (ref "C19") (pin "2") (pinfunction "2_2") (pintype "passive"))
      (node (ref "C2") (pin "2") (pinfunction "2_2") (pintype "passive"))
      (node (ref "C21") (pin "2") (pinfunction "2_2") (pintype "passive"))
      (node (ref "C23") (pin "2") (pinfunction "2_2") (pintype "passive"))
      (node (ref "C25") (pin "2") (pinfunction "2_2") (pintype "passive"))
      (node (ref "C27") (pin "2") (pinfunction "2_2") (pintype "passive"))
      (node (ref "C29") (pin "1") (pinfunction "1_1") (pintype "passive"))
      (node (ref "C3") (pin "2") (pinfunction "2_2") (pintype "passive"))
      (node (ref "C31") (pin "2") (pinfunction "2_2") (pintype "passive"))
      (node (ref "C32") (pin "2") (pinfunction "2_2") (pintype "passive"))
      (node (ref "C33") (pin "2") (pinfunction "2_2") (pintype "passive"))
      (node (ref "C37") (pin "2") (pinfunction "2_2") (pintype "passive"))
      (node (ref "C38") (pin "2") (pinfunction "2_2") (pintype "passive"))
      (node (ref "C39") (pin "2") (pinfunction "2_2") (pintype "passive"))
      (node (ref "C4") (pin "2") (pinfunction "2_2") (pintype "passive"))
      (node (ref "C40") (pin "2") (pinfunction "2_2") (pintype "passive"))
      (node (ref "C41") (pin "2") (pinfunction "2_2") (pintype "passive"))
      (node (ref "C42") (pin "2") (pinfunction "2_2") (pintype "passive"))
      (node (ref "C43") (pin "2") (pinfunction "2_2") (pintype "passive"))
      (node (ref "C44") (pin "2") (pinfunction "2_2") (pintype "passive"))
      (node (ref "C45") (pin "N") (pinfunction "NEG_N") (pintype "bidirectional"))
      (node (ref "C46") (pin "1") (pinfunction "1_1") (pintype "passive"))
      (node (ref "C47") (pin "1") (pinfunction "1_1") (pintype "passive"))
      (node (ref "C48") (pin "1") (pinfunction "1_1") (pintype "passive"))
      (node (ref "C49") (pin "1") (pinfunction "1_1") (pintype "passive"))
      (node (ref "C5") (pin "2") (pinfunction "2_2") (pintype "passive"))
      (node (ref "C50") (pin "1") (pinfunction "1_1") (pintype "passive"))
      (node (ref "C51") (pin "1") (pinfunction "1_1") (pintype "passive"))
      (node (ref "C52") (pin "1") (pinfunction "1_1") (pintype "passive"))
      (node (ref "C53") (pin "N") (pinfunction "NEG_N") (pintype "bidirectional"))
      (node (ref "C54") (pin "1") (pinfunction "1_1") (pintype "passive"))
      (node (ref "C6") (pin "2") (pinfunction "2_2") (pintype "passive"))
      (node (ref "C7") (pin "2") (pinfunction "2_2") (pintype "passive"))
      (node (ref "C8") (pin "2") (pinfunction "2_2") (pintype "passive"))
      (node (ref "C9") (pin "2") (pinfunction "2_2") (pintype "passive"))
      (node (ref "D1") (pin "CATHODE") (pinfunction "CATHODE_CATHODE") (pintype "bidirectional"))
      (node (ref "D10") (pin "3") (pinfunction "3_3") (pintype "bidirectional"))
      (node (ref "D11") (pin "3") (pinfunction "3_3") (pintype "bidirectional"))
      (node (ref "D12") (pin "CATHODE") (pinfunction "CATHODE_CATHODE") (pintype "bidirectional"))
      (node (ref "D4") (pin "3") (pinfunction "3_3") (pintype "bidirectional"))
      (node (ref "D5") (pin "3") (pinfunction "3_3") (pintype "bidirectional"))
      (node (ref "D6") (pin "3") (pinfunction "3_3") (pintype "bidirectional"))
      (node (ref "D7") (pin "3") (pinfunction "3_3") (pintype "bidirectional"))
      (node (ref "D8") (pin "3") (pinfunction "3_3") (pintype "bidirectional"))
      (node (ref "D9") (pin "3") (pinfunction "3_3") (pintype "bidirectional"))
      (node (ref "J1") (pin "5") (pinfunction "GND_5") (pintype "bidirectional"))
      (node (ref "J1") (pin "S1") (pinfunction "GND_S1") (pintype "bidirectional"))
      (node (ref "J1") (pin "S2") (pinfunction "GND_S2") (pintype "bidirectional"))
      (node (ref "J1") (pin "S3") (pinfunction "GND_S3") (pintype "bidirectional"))
      (node (ref "J1") (pin "S4") (pinfunction "GND_S4") (pintype "bidirectional"))
      (node (ref "LCD1") (pin "1") (pinfunction "VSS_1") (pintype "bidirectional"))
      (node (ref "R14") (pin "2") (pinfunction "2_2") (pintype "passive"))
      (node (ref "R17") (pin "2") (pinfunction "2_2") (pintype "passive"))
      (node (ref "R18") (pin "2") (pinfunction "2_2") (pintype "passive"))
      (node (ref "R20") (pin "1") (pinfunction "1_1") (pintype "passive"))
      (node (ref "R28") (pin "1") (pinfunction "1_1") (pintype "passive"))
      (node (ref "R30") (pin "2") (pinfunction "2_2") (pintype "passive"))
      (node (ref "R34") (pin "1") (pinfunction "1_1") (pintype "passive"))
      (node (ref "R38") (pin "2") (pinfunction "2_2") (pintype "passive"))
      (node (ref "SD1") (pin "3") (pinfunction "GND_3") (pintype "bidirectional"))
      (node (ref "SD1") (pin "SHIELD0") (pinfunction "GND_SHIELD0") (pintype "bidirectional"))
      (node (ref "SD1") (pin "SHIELD1") (pinfunction "GND_SHIELD1") (pintype "bidirectional"))
      (node (ref "SD1") (pin "SHIELD2") (pinfunction "GND_SHIELD2") (pintype "bidirectional"))
      (node (ref "SD1") (pin "SHIELD3") (pinfunction "GND_SHIELD3") (pintype "bidirectional"))
      (node (ref "SW2") (pin "1") (pinfunction "A_1") (pintype "bidirectional"))
      (node (ref "SW2") (pin "2") (pinfunction "A_2") (pintype "bidirectional"))
      (node (ref "SW3") (pin "1") (pinfunction "A_1") (pintype "bidirectional"))
      (node (ref "SW3") (pin "2") (pinfunction "A_2") (pintype "bidirectional"))
      (node (ref "SW4") (pin "1") (pinfunction "A_1") (pintype "bidirectional"))
      (node (ref "SW4") (pin "2") (pinfunction "A_2") (pintype "bidirectional"))
      (node (ref "SW5") (pin "1") (pinfunction "A_1") (pintype "bidirectional"))
      (node (ref "SW5") (pin "2") (pinfunction "A_2") (pintype "bidirectional"))
      (node (ref "U1") (pin "17") (pinfunction "VSS_17") (pintype "bidirectional"))
      (node (ref "U1") (pin "27") (pinfunction "VSS_27") (pintype "bidirectional"))
      (node (ref "U1") (pin "39") (pinfunction "VSS_39") (pintype "bidirectional"))
      (node (ref "U1") (pin "5") (pinfunction "VSS_5") (pintype "bidirectional"))
      (node (ref "U1") (pin "6") (pinfunction "BOE'_6") (pintype "bidirectional"))
      (node (ref "U10") (pin "4") (pinfunction "VSS_4") (pintype "bidirectional"))
      (node (ref "U11") (pin "10") (pinfunction "ADR1_10") (pintype "bidirectional"))
      (node (ref "U11") (pin "6") (pinfunction "VDD_6") (pintype "bidirectional"))
      (node (ref "U11") (pin "9") (pinfunction "ADR0_9") (pintype "bidirectional"))
      (node (ref "U12") (pin "6") (pinfunction "VDD_6") (pintype "bidirectional"))
      (node (ref "U13") (pin "P$4") (pinfunction "GND_P$4") (pintype "bidirectional"))
      (node (ref "U13") (pin "P$5") (pinfunction "A2_P$5") (pintype "bidirectional"))
      (node (ref "U13") (pin "P$6") (pinfunction "A1_P$6") (pintype "bidirectional"))
      (node (ref "U13") (pin "P$7") (pinfunction "A0_P$7") (pintype "bidirectional"))
      (node (ref "U14") (pin "P$4") (pinfunction "GND_P$4") (pintype "bidirectional"))
      (node (ref "U14") (pin "P$5") (pinfunction "A2_P$5") (pintype "bidirectional"))
      (node (ref "U14") (pin "P$6") (pinfunction "A1_P$6") (pintype "bidirectional"))
      (node (ref "U15") (pin "P$4") (pinfunction "GND_P$4") (pintype "bidirectional"))
      (node (ref "U15") (pin "P$5") (pinfunction "A2_P$5") (pintype "bidirectional"))
      (node (ref "U15") (pin "P$7") (pinfunction "A0_P$7") (pintype "bidirectional"))
      (node (ref "U16") (pin "P$4") (pinfunction "GND_P$4") (pintype "bidirectional"))
      (node (ref "U16") (pin "P$5") (pinfunction "A2_P$5") (pintype "bidirectional"))
      (node (ref "U17") (pin "P$4") (pinfunction "GND_P$4") (pintype "bidirectional"))
      (node (ref "U17") (pin "P$6") (pinfunction "A1_P$6") (pintype "bidirectional"))
      (node (ref "U17") (pin "P$7") (pinfunction "A0_P$7") (pintype "bidirectional"))
      (node (ref "U18") (pin "P$4") (pinfunction "GND_P$4") (pintype "bidirectional"))
      (node (ref "U18") (pin "P$6") (pinfunction "A1_P$6") (pintype "bidirectional"))
      (node (ref "U19") (pin "P$4") (pinfunction "GND_P$4") (pintype "bidirectional"))
      (node (ref "U19") (pin "P$7") (pinfunction "A0_P$7") (pintype "bidirectional"))
      (node (ref "U2") (pin "2") (pinfunction "A1_2") (pintype "bidirectional"))
      (node (ref "U2") (pin "3") (pinfunction "A2_3") (pintype "bidirectional"))
      (node (ref "U2") (pin "4") (pinfunction "GND_4") (pintype "bidirectional"))
      (node (ref "U2") (pin "7") (pinfunction "WP_7") (pintype "bidirectional"))
      (node (ref "U20") (pin "P$4") (pinfunction "GND_P$4") (pintype "bidirectional"))
      (node (ref "U21") (pin "2") (pinfunction "SOURCE_2") (pintype "bidirectional"))
      (node (ref "U3") (pin "IN") (pinfunction "GND_IN") (pintype "bidirectional"))
      (node (ref "U4") (pin "13") (pinfunction "GND_13") (pintype "bidirectional"))
      (node (ref "U4") (pin "3") (pinfunction "GND_3") (pintype "bidirectional"))
      (node (ref "U4") (pin "PAD") (pinfunction "GND_PAD") (pintype "bidirectional"))
      (node (ref "U5") (pin "15") (pinfunction "SYSOFF_15") (pintype "bidirectional"))
      (node (ref "U5") (pin "8") (pinfunction "VSS_8") (pintype "bidirectional"))
      (node (ref "U5") (pin "PAD0") (pinfunction "VSS_PAD0") (pintype "bidirectional"))
      (node (ref "U5") (pin "PAD1") (pinfunction "VSS_PAD1") (pintype "bidirectional"))
      (node (ref "U6") (pin "2") (pinfunction "GND_2") (pintype "bidirectional"))
      (node (ref "U7") (pin "2") (pinfunction "SOURCE_2") (pintype "bidirectional"))
      (node (ref "U9") (pin "2") (pinfunction "GND_2") (pintype "bidirectional"))
    )
    (net (code "17") (name "/IRQ") (class "Default")
      (node (ref "R2") (pin "1") (pinfunction "1_1") (pintype "passive"))
      (node (ref "SD1") (pin "1") (pinfunction "IRQ_1") (pintype "bidirectional"))
    )
    (net (code "18") (name "/LCD_CS") (class "Default")
      (node (ref "LCD1") (pin "16") (pinfunction "BK_GND_16") (pintype "bidirectional"))
      (node (ref "U1") (pin "4") (pinfunction "P7_4") (pintype "bidirectional"))
    )
    (net (code "19") (name "/LCD_SCL") (class "Default")
      (node (ref "LCD1") (pin "12") (pinfunction "D5_12") (pintype "bidirectional"))
      (node (ref "U1") (pin "1") (pinfunction "P4_1") (pintype "bidirectional"))
    )
    (net (code "20") (name "/LCD_SDI") (class "Default")
      (node (ref "LCD1") (pin "14") (pinfunction "D7_14") (pintype "bidirectional"))
      (node (ref "U1") (pin "3") (pinfunction "P6_3") (pintype "bidirectional"))
    )
    (net (code "21") (name "/LCD_SDO") (class "Default")
      (node (ref "LCD1") (pin "13") (pinfunction "D6_13") (pintype "bidirectional"))
      (node (ref "U1") (pin "2") (pinfunction "P5_2") (pintype "bidirectional"))
    )
    (net (code "22") (name "/P12") (class "Default")
      (node (ref "U1") (pin "13") (pinfunction "P12_13") (pintype "bidirectional"))
    )
    (net (code "23") (name "/P13") (class "Default")
      (node (ref "U1") (pin "14") (pinfunction "P13_14") (pintype "bidirectional"))
    )
    (net (code "24") (name "/P14") (class "Default")
      (node (ref "U1") (pin "15") (pinfunction "P14_15") (pintype "bidirectional"))
    )
    (net (code "25") (name "/P15") (class "Default")
      (node (ref "U1") (pin "16") (pinfunction "P15_16") (pintype "bidirectional"))
    )
    (net (code "26") (name "/P16") (class "Default")
      (node (ref "U1") (pin "19") (pinfunction "P16_19") (pintype "bidirectional"))
    )
    (net (code "27") (name "/P17") (class "Default")
      (node (ref "U1") (pin "20") (pinfunction "P17_20") (pintype "bidirectional"))
    )
    (net (code "28") (name "/P18") (class "Default")
      (node (ref "U1") (pin "21") (pinfunction "P18_21") (pintype "bidirectional"))
    )
    (net (code "29") (name "/PGOOD") (class "Default")
      (node (ref "R16") (pin "2") (pinfunction "2_2") (pintype "passive"))
      (node (ref "U5") (pin "7") (pinfunction "~{PGOOD}_7") (pintype "bidirectional"))
    )
    (net (code "30") (name "/PWREN") (class "Default")
      (node (ref "U5") (pin "6") (pinfunction "EN1_6") (pintype "bidirectional"))
      (node (ref "U6") (pin "4") (pinfunction "2Y_4") (pintype "bidirectional"))
    )
    (net (code "31") (name "/PWR_SW") (class "Default")
      (node (ref "D3") (pin "ANODE") (pinfunction "ANODE_ANODE") (pintype "bidirectional"))
      (node (ref "R26") (pin "1") (pinfunction "1_1") (pintype "passive"))
      (node (ref "R27") (pin "1") (pinfunction "1_1") (pintype "passive"))
      (node (ref "U1") (pin "32") (pinfunction "P25_32") (pintype "bidirectional"))
    )
    (net (code "32") (name "/RES") (class "Default")
      (node (ref "R1") (pin "1") (pinfunction "1_1") (pintype "passive"))
      (node (ref "SW1") (pin "3") (pinfunction "B_3") (pintype "bidirectional"))
      (node (ref "SW1") (pin "4") (pinfunction "B_4") (pintype "bidirectional"))
      (node (ref "U1") (pin "7") (pinfunction "RES'_7") (pintype "bidirectional"))
    )
    (net (code "33") (name "/RTC_X1") (class "Default")
      (node (ref "U10") (pin "1") (pinfunction "X1_1") (pintype "bidirectional"))
      (node (ref "X2") (pin "1") (pinfunction "P$1_1") (pintype "bidirectional"))
    )
    (net (code "34") (name "/RTC_X2") (class "Default")
      (node (ref "U10") (pin "2") (pinfunction "X2_2") (pintype "bidirectional"))
      (node (ref "X2") (pin "4") (pinfunction "P$2_4") (pintype "bidirectional"))
    )
    (net (code "35") (name "/RTS") (class "Default")
      (node (ref "C12") (pin "1") (pinfunction "1_1") (pintype "passive"))
      (node (ref "U4") (pin "16") (pinfunction "RTS#_16") (pintype "bidirectional"))
    )
    (net (code "36") (name "/RX") (class "Default")
      (node (ref "U1") (pin "37") (pinfunction "P30_37") (pintype "bidirectional"))
      (node (ref "U4") (pin "2") (pinfunction "RXD_2") (pintype "bidirectional"))
    )
    (net (code "37") (name "/SCL") (class "Default")
      (node (ref "R8") (pin "1") (pinfunction "1_1") (pintype "passive"))
      (node (ref "U1") (pin "35") (pinfunction "P28_35") (pintype "bidirectional"))
      (node (ref "U10") (pin "6") (pinfunction "SCL_6") (pintype "bidirectional"))
      (node (ref "U2") (pin "6") (pinfunction "SCL_6") (pintype "bidirectional"))
      (node (ref "U9") (pin "5") (pinfunction "SCL_5") (pintype "bidirectional"))
    )
    (net (code "38") (name "/SCL_ADC") (class "Default")
      (node (ref "U1") (pin "10") (pinfunction "P9_10") (pintype "bidirectional"))
      (node (ref "U11") (pin "8") (pinfunction "SCL_8") (pintype "bidirectional"))
      (node (ref "U12") (pin "8") (pinfunction "SCL_8") (pintype "bidirectional"))
      (node (ref "U13") (pin "P$2") (pinfunction "SCL_P$2") (pintype "bidirectional"))
      (node (ref "U14") (pin "P$2") (pinfunction "SCL_P$2") (pintype "bidirectional"))
      (node (ref "U15") (pin "P$2") (pinfunction "SCL_P$2") (pintype "bidirectional"))
      (node (ref "U16") (pin "P$2") (pinfunction "SCL_P$2") (pintype "bidirectional"))
      (node (ref "U17") (pin "P$2") (pinfunction "SCL_P$2") (pintype "bidirectional"))
      (node (ref "U18") (pin "P$2") (pinfunction "SCL_P$2") (pintype "bidirectional"))
      (node (ref "U19") (pin "P$2") (pinfunction "SCL_P$2") (pintype "bidirectional"))
      (node (ref "U20") (pin "P$2") (pinfunction "SCL_P$2") (pintype "bidirectional"))
    )
    (net (code "39") (name "/SDA") (class "Default")
      (node (ref "R9") (pin "1") (pinfunction "1_1") (pintype "passive"))
      (node (ref "U1") (pin "36") (pinfunction "P29_36") (pintype "bidirectional"))
      (node (ref "U10") (pin "5") (pinfunction "SDA_5") (pintype "bidirectional"))
      (node (ref "U2") (pin "5") (pinfunction "SDA_5") (pintype "bidirectional"))
      (node (ref "U9") (pin "4") (pinfunction "SDA_4") (pintype "bidirectional"))
    )
    (net (code "40") (name "/SDA_ADC") (class "Default")
      (node (ref "U1") (pin "11") (pinfunction "P10_11") (pintype "bidirectional"))
      (node (ref "U11") (pin "7") (pinfunction "SDA_7") (pintype "bidirectional"))
      (node (ref "U12") (pin "7") (pinfunction "SDA_7") (pintype "bidirectional"))
      (node (ref "U13") (pin "P$1") (pinfunction "SDA_P$1") (pintype "bidirectional"))
      (node (ref "U14") (pin "P$1") (pinfunction "SDA_P$1") (pintype "bidirectional"))
      (node (ref "U15") (pin "P$1") (pinfunction "SDA_P$1") (pintype "bidirectional"))
      (node (ref "U16") (pin "P$1") (pinfunction "SDA_P$1") (pintype "bidirectional"))
      (node (ref "U17") (pin "P$1") (pinfunction "SDA_P$1") (pintype "bidirectional"))
      (node (ref "U18") (pin "P$1") (pinfunction "SDA_P$1") (pintype "bidirectional"))
      (node (ref "U19") (pin "P$1") (pinfunction "SDA_P$1") (pintype "bidirectional"))
      (node (ref "U20") (pin "P$1") (pinfunction "SDA_P$1") (pintype "bidirectional"))
    )
    (net (code "41") (name "/SD_CS") (class "Default")
      (node (ref "R6") (pin "1") (pinfunction "1_1") (pintype "passive"))
      (node (ref "SD1") (pin "7") (pinfunction "CS_7") (pintype "bidirectional"))
      (node (ref "U1") (pin "44") (pinfunction "P3_44") (pintype "bidirectional"))
    )
    (net (code "42") (name "/SD_DI") (class "Default")
      (node (ref "R5") (pin "1") (pinfunction "1_1") (pintype "passive"))
      (node (ref "SD1") (pin "6") (pinfunction "DI_6") (pintype "bidirectional"))
      (node (ref "U1") (pin "43") (pinfunction "P2_43") (pintype "bidirectional"))
    )
    (net (code "43") (name "/SD_DO") (class "Default")
      (node (ref "R3") (pin "1") (pinfunction "1_1") (pintype "passive"))
      (node (ref "SD1") (pin "2") (pinfunction "D0_2") (pintype "bidirectional"))
      (node (ref "U1") (pin "41") (pinfunction "P0_41") (pintype "bidirectional"))
    )
    (net (code "44") (name "/SD_RW") (class "Default")
      (node (ref "R7") (pin "1") (pinfunction "1_1") (pintype "passive"))
      (node (ref "SD1") (pin "8") (pinfunction "RW_8") (pintype "bidirectional"))
    )
    (net (code "45") (name "/SD_SCLK") (class "Default")
      (node (ref "R4") (pin "1") (pinfunction "1_1") (pintype "passive"))
      (node (ref "SD1") (pin "4") (pinfunction "SCLK_4") (pintype "bidirectional"))
      (node (ref "U1") (pin "42") (pinfunction "P1_42") (pintype "bidirectional"))
    )
    (net (code "46") (name "/SHT_DRAIN") (class "Default")
      (node (ref "R36") (pin "1") (pinfunction "1_1") (pintype "passive"))
      (node (ref "U1") (pin "12") (pinfunction "P11_12") (pintype "bidirectional"))
      (node (ref "U21") (pin "1") (pinfunction "GATE_1") (pintype "bidirectional"))
    )
    (net (code "47") (name "/SLEEP") (class "Default")
      (node (ref "U5") (pin "4") (pinfunction "~{CE}_4") (pintype "bidirectional"))
      (node (ref "U6") (pin "6") (pinfunction "1Y_6") (pintype "bidirectional"))
    )
    (net (code "48") (name "/SW_DWN") (class "Default")
      (node (ref "R23") (pin "1") (pinfunction "1_1") (pintype "passive"))
      (node (ref "SW4") (pin "3") (pinfunction "B_3") (pintype "bidirectional"))
      (node (ref "SW4") (pin "4") (pinfunction "B_4") (pintype "bidirectional"))
      (node (ref "U1") (pin "31") (pinfunction "P24_31") (pintype "bidirectional"))
    )
    (net (code "49") (name "/SW_SEL") (class "Default")
      (node (ref "R22") (pin "1") (pinfunction "1_1") (pintype "passive"))
      (node (ref "SW3") (pin "3") (pinfunction "B_3") (pintype "bidirectional"))
      (node (ref "SW3") (pin "4") (pinfunction "B_4") (pintype "bidirectional"))
      (node (ref "U1") (pin "26") (pinfunction "P23_26") (pintype "bidirectional"))
    )
    (net (code "50") (name "/SW_UP") (class "Default")
      (node (ref "R21") (pin "1") (pinfunction "1_1") (pintype "passive"))
      (node (ref "SW2") (pin "3") (pinfunction "B_3") (pintype "bidirectional"))
      (node (ref "SW2") (pin "4") (pinfunction "B_4") (pintype "bidirectional"))
      (node (ref "U1") (pin "25") (pinfunction "P22_25") (pintype "bidirectional"))
    )
    (net (code "51") (name "/SYS_V") (class "Default")
      (node (ref "C32") (pin "1") (pinfunction "1_1") (pintype "passive"))
      (node (ref "C34") (pin "1") (pinfunction "1_1") (pintype "passive"))
      (node (ref "R24") (pin "2") (pinfunction "2_2") (pintype "passive"))
      (node (ref "R25") (pin "2") (pinfunction "2_2") (pintype "passive"))
      (node (ref "U10") (pin "3") (pinfunction "V_BACK_3") (pintype "bidirectional"))
      (node (ref "U5") (pin "10") (pinfunction "OUT_10") (pintype "bidirectional"))
      (node (ref "U5") (pin "11") (pinfunction "OUT_11") (pintype "bidirectional"))
      (node (ref "U8") (pin "2") (pinfunction "SOURCE_2") (pintype "bidirectional"))
    )
    (net (code "52") (name "/SYS_V_SW") (class "Default")
      (node (ref "C7") (pin "1") (pinfunction "1_1") (pintype "passive"))
      (node (ref "C9") (pin "1") (pinfunction "1_1") (pintype "passive"))
      (node (ref "U3") (pin "OUT") (pinfunction "IN_OUT") (pintype "bidirectional"))
      (node (ref "U8") (pin "3") (pinfunction "DRAIN_3") (pintype "bidirectional"))
    )
    (net (code "53") (name "/TP_T+_0") (class "Default")
      (node (ref "C16") (pin "2") (pinfunction "2_2") (pintype "passive"))
      (node (ref "L3") (pin "1") (pinfunction "P$1_1") (pintype "bidirectional"))
      (node (ref "U11") (pin "1") (pinfunction "CH1+_1") (pintype "bidirectional"))
    )
    (net (code "54") (name "/TP_T+_1") (class "Default")
      (node (ref "C18") (pin "2") (pinfunction "2_2") (pintype "passive"))
      (node (ref "L4") (pin "1") (pinfunction "P$1_1") (pintype "bidirectional"))
      (node (ref "U11") (pin "3") (pinfunction "CH2+_3") (pintype "bidirectional"))
    )
    (net (code "55") (name "/TP_T+_2") (class "Default")
      (node (ref "C20") (pin "2") (pinfunction "2_2") (pintype "passive"))
      (node (ref "L6") (pin "1") (pinfunction "P$1_1") (pintype "bidirectional"))
      (node (ref "U11") (pin "11") (pinfunction "CH3+_11") (pintype "bidirectional"))
    )
    (net (code "56") (name "/TP_T+_3") (class "Default")
      (node (ref "C22") (pin "2") (pinfunction "2_2") (pintype "passive"))
      (node (ref "L8") (pin "1") (pinfunction "P$1_1") (pintype "bidirectional"))
      (node (ref "U11") (pin "13") (pinfunction "CH4+_13") (pintype "bidirectional"))
    )
    (net (code "57") (name "/TP_T+_4") (class "Default")
      (node (ref "C24") (pin "2") (pinfunction "2_2") (pintype "passive"))
      (node (ref "L10") (pin "1") (pinfunction "P$1_1") (pintype "bidirectional"))
      (node (ref "U12") (pin "1") (pinfunction "CH1+_1") (pintype "bidirectional"))
    )
    (net (code "58") (name "/TP_T+_5") (class "Default")
      (node (ref "C26") (pin "2") (pinfunction "2_2") (pintype "passive"))
      (node (ref "L12") (pin "1") (pinfunction "P$1_1") (pintype "bidirectional"))
      (node (ref "U12") (pin "3") (pinfunction "CH2+_3") (pintype "bidirectional"))
    )
    (net (code "59") (name "/TP_T+_6") (class "Default")
      (node (ref "C28") (pin "2") (pinfunction "2_2") (pintype "passive"))
      (node (ref "L14") (pin "1") (pinfunction "P$1_1") (pintype "bidirectional"))
      (node (ref "U12") (pin "11") (pinfunction "CH3+_11") (pintype "bidirectional"))
    )
    (net (code "60") (name "/TP_T+_7") (class "Default")
      (node (ref "C30") (pin "2") (pinfunction "2_2") (pintype "passive"))
      (node (ref "L16") (pin "1") (pinfunction "P$1_1") (pintype "bidirectional"))
      (node (ref "U12") (pin "13") (pinfunction "CH4+_13") (pintype "bidirectional"))
    )
    (net (code "61") (name "/TP_T-_0") (class "Default")
      (node (ref "C16") (pin "1") (pinfunction "1_1") (pintype "passive"))
      (node (ref "L2") (pin "2") (pinfunction "P$2_2") (pintype "bidirectional"))
      (node (ref "U11") (pin "2") (pinfunction "CH1-_2") (pintype "bidirectional"))
    )
    (net (code "62") (name "/TP_T-_1") (class "Default")
      (node (ref "C18") (pin "1") (pinfunction "1_1") (pintype "passive"))
      (node (ref "L5") (pin "2") (pinfunction "P$2_2") (pintype "bidirectional"))
      (node (ref "U11") (pin "4") (pinfunction "CH2-_4") (pintype "bidirectional"))
    )
    (net (code "63") (name "/TP_T-_2") (class "Default")
      (node (ref "C20") (pin "1") (pinfunction "1_1") (pintype "passive"))
      (node (ref "L7") (pin "2") (pinfunction "P$2_2") (pintype "bidirectional"))
      (node (ref "U11") (pin "12") (pinfunction "CH3-_12") (pintype "bidirectional"))
    )
    (net (code "64") (name "/TP_T-_3") (class "Default")
      (node (ref "C22") (pin "1") (pinfunction "1_1") (pintype "passive"))
      (node (ref "L9") (pin "2") (pinfunction "P$2_2") (pintype "bidirectional"))
      (node (ref "U11") (pin "14") (pinfunction "CH4-_14") (pintype "bidirectional"))
    )
    (net (code "65") (name "/TP_T-_4") (class "Default")
      (node (ref "C24") (pin "1") (pinfunction "1_1") (pintype "passive"))
      (node (ref "L11") (pin "2") (pinfunction "P$2_2") (pintype "bidirectional"))
      (node (ref "U12") (pin "2") (pinfunction "CH1-_2") (pintype "bidirectional"))
    )
    (net (code "66") (name "/TP_T-_5") (class "Default")
      (node (ref "C26") (pin "1") (pinfunction "1_1") (pintype "passive"))
      (node (ref "L13") (pin "2") (pinfunction "P$2_2") (pintype "bidirectional"))
      (node (ref "U12") (pin "4") (pinfunction "CH2-_4") (pintype "bidirectional"))
    )
    (net (code "67") (name "/TP_T-_6") (class "Default")
      (node (ref "C28") (pin "1") (pinfunction "1_1") (pintype "passive"))
      (node (ref "L15") (pin "2") (pinfunction "P$2_2") (pintype "bidirectional"))
      (node (ref "U12") (pin "12") (pinfunction "CH3-_12") (pintype "bidirectional"))
    )
    (net (code "68") (name "/TP_T-_7") (class "Default")
      (node (ref "C30") (pin "1") (pinfunction "1_1") (pintype "passive"))
      (node (ref "L17") (pin "2") (pinfunction "P$2_2") (pintype "bidirectional"))
      (node (ref "U12") (pin "14") (pinfunction "CH4-_14") (pintype "bidirectional"))
    )
    (net (code "69") (name "/TS") (class "Default")
      (node (ref "R14") (pin "1") (pinfunction "1_1") (pintype "passive"))
      (node (ref "U5") (pin "1") (pinfunction "TS_1") (pintype "bidirectional"))
    )
    (net (code "70") (name "/TX") (class "Default")
      (node (ref "U1") (pin "38") (pinfunction "P31_38") (pintype "bidirectional"))
      (node (ref "U4") (pin "15") (pinfunction "TXD_15") (pintype "bidirectional"))
    )
    (net (code "71") (name "/TXRX_LED") (class "Default")
      (node (ref "D2") (pin "CATHODE") (pinfunction "CATHODE_CATHODE") (pintype "bidirectional"))
      (node (ref "U4") (pin "12") (pinfunction "CBUS0_12") (pintype "bidirectional"))
    )
    (net (code "72") (name "/USBDM") (class "Default")
      (node (ref "R10") (pin "2") (pinfunction "2_2") (pintype "passive"))
      (node (ref "U4") (pin "7") (pinfunction "USBDM_7") (pintype "bidirectional"))
    )
    (net (code "73") (name "/USBDP") (class "Default")
      (node (ref "R11") (pin "2") (pinfunction "2_2") (pintype "passive"))
      (node (ref "U4") (pin "6") (pinfunction "USBDP_6") (pintype "bidirectional"))
    )
    (net (code "74") (name "/USB_RST") (class "Default")
      (node (ref "C12") (pin "2") (pinfunction "2_2") (pintype "passive"))
      (node (ref "R33") (pin "2") (pinfunction "2_2") (pintype "passive"))
      (node (ref "SW1") (pin "1") (pinfunction "A_1") (pintype "bidirectional"))
      (node (ref "SW1") (pin "2") (pinfunction "A_2") (pintype "bidirectional"))
      (node (ref "U1") (pin "9") (pinfunction "P8_9") (pintype "bidirectional"))
    )
    (net (code "75") (name "/USB_V0") (class "Default")
      (node (ref "J1") (pin "1") (pinfunction "5V_1") (pintype "bidirectional"))
      (node (ref "L1") (pin "1") (pinfunction "1_1") (pintype "passive"))
    )
    (net (code "76") (name "/USB_V1") (class "Default")
      (node (ref "C13") (pin "1") (pinfunction "1_1") (pintype "passive"))
      (node (ref "C14") (pin "1") (pinfunction "1_1") (pintype "passive"))
      (node (ref "C33") (pin "1") (pinfunction "1_1") (pintype "passive"))
      (node (ref "L1") (pin "2") (pinfunction "2_2") (pintype "passive"))
      (node (ref "R12") (pin "1") (pinfunction "1_1") (pintype "passive"))
      (node (ref "R13") (pin "1") (pinfunction "1_1") (pintype "passive"))
      (node (ref "U4") (pin "10") (pinfunction "VCC_10") (pintype "bidirectional"))
      (node (ref "U5") (pin "13") (pinfunction "IN_13") (pintype "bidirectional"))
    )
    (net (code "77") (name "/VBATT") (class "Default")
      (node (ref "BATT1") (pin "2") (pinfunction "2_2") (pintype "passive"))
      (node (ref "C31") (pin "1") (pinfunction "1_1") (pintype "passive"))
      (node (ref "R29") (pin "1") (pinfunction "1_1") (pintype "passive"))
      (node (ref "U5") (pin "2") (pinfunction "BAT_2") (pintype "bidirectional"))
      (node (ref "U5") (pin "3") (pinfunction "BAT_3") (pintype "bidirectional"))
    )
    (net (code "78") (name "/X0") (class "Default")
      (node (ref "U1") (pin "29") (pinfunction "X0_29") (pintype "bidirectional"))
      (node (ref "X1") (pin "P$1") (pinfunction "P$1_P$1") (pintype "bidirectional"))
    )
    (net (code "79") (name "/X1") (class "Default")
      (node (ref "U1") (pin "28") (pinfunction "X1_28") (pintype "bidirectional"))
      (node (ref "X1") (pin "P$2") (pinfunction "P$2_P$2") (pintype "bidirectional"))
    )
    (net (code "80") (name "/~{PWREN}") (class "Default")
      (node (ref "R19") (pin "1") (pinfunction "1_1") (pintype "passive"))
      (node (ref "U4") (pin "14") (pinfunction "CBUS3_14") (pintype "bidirectional"))
      (node (ref "U6") (pin "3") (pinfunction "2A_3") (pintype "bidirectional"))
    )
    (net (code "81") (name "/~{SLEEP}") (class "Default")
      (node (ref "U1") (pin "23") (pinfunction "P20_23") (pintype "bidirectional"))
      (node (ref "U4") (pin "11") (pinfunction "CBUS1_11") (pintype "bidirectional"))
      (node (ref "U6") (pin "1") (pinfunction "1A_1") (pintype "bidirectional"))
    )
    (net (code "82") (name "Net-(C35-Pad1)") (class "Default")
      (node (ref "C35") (pin "1") (pinfunction "1_1") (pintype "passive"))
      (node (ref "D3") (pin "CATHODE") (pinfunction "CATHODE_CATHODE") (pintype "bidirectional"))
      (node (ref "R25") (pin "1") (pinfunction "1_1") (pintype "passive"))
      (node (ref "SW5") (pin "3") (pinfunction "B_3") (pintype "bidirectional"))
      (node (ref "SW5") (pin "4") (pinfunction "B_4") (pintype "bidirectional"))
    )
    (net (code "83") (name "Net-(D1-PadANODE)") (class "Default")
      (node (ref "D1") (pin "ANODE") (pinfunction "ANODE_ANODE") (pintype "bidirectional"))
      (node (ref "R13") (pin "2") (pinfunction "2_2") (pintype "passive"))
    )
    (net (code "84") (name "Net-(D2-PadANODE)") (class "Default")
      (node (ref "D2") (pin "ANODE") (pinfunction "ANODE_ANODE") (pintype "bidirectional"))
      (node (ref "R12") (pin "2") (pinfunction "2_2") (pintype "passive"))
    )
    (net (code "85") (name "Net-(D12-PadANODE)") (class "Default")
      (node (ref "D12") (pin "ANODE") (pinfunction "ANODE_ANODE") (pintype "bidirectional"))
      (node (ref "R32") (pin "2") (pinfunction "2_2") (pintype "passive"))
    )
    (net (code "86") (name "Net-(L2-P$1)") (class "Default")
      (node (ref "D4") (pin "2") (pinfunction "2_2") (pintype "bidirectional"))
      (node (ref "L2") (pin "1") (pinfunction "P$1_1") (pintype "bidirectional"))
      (node (ref "TC1") (pin "2") (pinfunction "2_2") (pintype "passive"))
    )
    (net (code "87") (name "Net-(L3-P$2)") (class "Default")
      (node (ref "D4") (pin "1") (pinfunction "1_1") (pintype "bidirectional"))
      (node (ref "L3") (pin "2") (pinfunction "P$2_2") (pintype "bidirectional"))
      (node (ref "TC1") (pin "1") (pinfunction "1_1") (pintype "passive"))
    )
    (net (code "88") (name "Net-(L4-P$2)") (class "Default")
      (node (ref "D5") (pin "1") (pinfunction "1_1") (pintype "bidirectional"))
      (node (ref "L4") (pin "2") (pinfunction "P$2_2") (pintype "bidirectional"))
      (node (ref "TC2") (pin "1") (pinfunction "1_1") (pintype "passive"))
    )
    (net (code "89") (name "Net-(L5-P$1)") (class "Default")
      (node (ref "D5") (pin "2") (pinfunction "2_2") (pintype "bidirectional"))
      (node (ref "L5") (pin "1") (pinfunction "P$1_1") (pintype "bidirectional"))
      (node (ref "TC2") (pin "2") (pinfunction "2_2") (pintype "passive"))
    )
    (net (code "90") (name "Net-(L6-P$2)") (class "Default")
      (node (ref "D6") (pin "1") (pinfunction "1_1") (pintype "bidirectional"))
      (node (ref "L6") (pin "2") (pinfunction "P$2_2") (pintype "bidirectional"))
      (node (ref "TC3") (pin "1") (pinfunction "1_1") (pintype "passive"))
    )
    (net (code "91") (name "Net-(L7-P$1)") (class "Default")
      (node (ref "D6") (pin "2") (pinfunction "2_2") (pintype "bidirectional"))
      (node (ref "L7") (pin "1") (pinfunction "P$1_1") (pintype "bidirectional"))
      (node (ref "TC3") (pin "2") (pinfunction "2_2") (pintype "passive"))
    )
    (net (code "92") (name "Net-(L8-P$2)") (class "Default")
      (node (ref "D7") (pin "1") (pinfunction "1_1") (pintype "bidirectional"))
      (node (ref "L8") (pin "2") (pinfunction "P$2_2") (pintype "bidirectional"))
      (node (ref "TC4") (pin "1") (pinfunction "1_1") (pintype "passive"))
    )
    (net (code "93") (name "Net-(L9-P$1)") (class "Default")
      (node (ref "D7") (pin "2") (pinfunction "2_2") (pintype "bidirectional"))
      (node (ref "L9") (pin "1") (pinfunction "P$1_1") (pintype "bidirectional"))
      (node (ref "TC4") (pin "2") (pinfunction "2_2") (pintype "passive"))
    )
    (net (code "94") (name "Net-(L10-P$2)") (class "Default")
      (node (ref "D8") (pin "1") (pinfunction "1_1") (pintype "bidirectional"))
      (node (ref "L10") (pin "2") (pinfunction "P$2_2") (pintype "bidirectional"))
      (node (ref "TC5") (pin "1") (pinfunction "1_1") (pintype "passive"))
    )
    (net (code "95") (name "Net-(L11-P$1)") (class "Default")
      (node (ref "D8") (pin "2") (pinfunction "2_2") (pintype "bidirectional"))
      (node (ref "L11") (pin "1") (pinfunction "P$1_1") (pintype "bidirectional"))
      (node (ref "TC5") (pin "2") (pinfunction "2_2") (pintype "passive"))
    )
    (net (code "96") (name "Net-(L12-P$2)") (class "Default")
      (node (ref "D9") (pin "1") (pinfunction "1_1") (pintype "bidirectional"))
      (node (ref "L12") (pin "2") (pinfunction "P$2_2") (pintype "bidirectional"))
      (node (ref "TC6") (pin "1") (pinfunction "1_1") (pintype "passive"))
    )
    (net (code "97") (name "Net-(L13-P$1)") (class "Default")
      (node (ref "D9") (pin "2") (pinfunction "2_2") (pintype "bidirectional"))
      (node (ref "L13") (pin "1") (pinfunction "P$1_1") (pintype "bidirectional"))
      (node (ref "TC6") (pin "2") (pinfunction "2_2") (pintype "passive"))
    )
    (net (code "98") (name "Net-(L14-P$2)") (class "Default")
      (node (ref "D10") (pin "1") (pinfunction "1_1") (pintype "bidirectional"))
      (node (ref "L14") (pin "2") (pinfunction "P$2_2") (pintype "bidirectional"))
      (node (ref "TC7") (pin "1") (pinfunction "1_1") (pintype "passive"))
    )
    (net (code "99") (name "Net-(L15-P$1)") (class "Default")
      (node (ref "D10") (pin "2") (pinfunction "2_2") (pintype "bidirectional"))
      (node (ref "L15") (pin "1") (pinfunction "P$1_1") (pintype "bidirectional"))
      (node (ref "TC7") (pin "2") (pinfunction "2_2") (pintype "passive"))
    )
    (net (code "100") (name "Net-(L16-P$2)") (class "Default")
      (node (ref "D11") (pin "1") (pinfunction "1_1") (pintype "bidirectional"))
      (node (ref "L16") (pin "2") (pinfunction "P$2_2") (pintype "bidirectional"))
      (node (ref "TC8") (pin "1") (pinfunction "1_1") (pintype "passive"))
    )
    (net (code "101") (name "Net-(L17-P$1)") (class "Default")
      (node (ref "D11") (pin "2") (pinfunction "2_2") (pintype "bidirectional"))
      (node (ref "L17") (pin "1") (pinfunction "P$1_1") (pintype "bidirectional"))
      (node (ref "TC8") (pin "2") (pinfunction "2_2") (pintype "passive"))
    )
    (net (code "102") (name "Net-(L18-P$1)") (class "Default")
      (node (ref "C23") (pin "1") (pinfunction "1_1") (pintype "passive"))
      (node (ref "L18") (pin "1") (pinfunction "P$1_1") (pintype "bidirectional"))
      (node (ref "R35") (pin "2") (pinfunction "2_2") (pintype "passive"))
    )
    (net (code "103") (name "Net-(OP1-Pad2)") (class "Default")
      (node (ref "OP1") (pin "2") (pinfunction "2_2") (pintype "bidirectional"))
      (node (ref "R28") (pin "2") (pinfunction "2_2") (pintype "passive"))
    )
    (net (code "104") (name "Net-(OP1-Pad4)") (class "Default")
      (node (ref "OP1") (pin "4") (pinfunction "4_4") (pintype "bidirectional"))
      (node (ref "R34") (pin "2") (pinfunction "2_2") (pintype "passive"))
    )
    (net (code "105") (name "Net-(U5-ILM)") (class "Default")
      (node (ref "R17") (pin "1") (pinfunction "1_1") (pintype "passive"))
      (node (ref "U5") (pin "12") (pinfunction "ILM_12") (pintype "bidirectional"))
    )
    (net (code "106") (name "Net-(U5-ISET)") (class "Default")
      (node (ref "R18") (pin "1") (pinfunction "1_1") (pintype "passive"))
      (node (ref "U5") (pin "16") (pinfunction "ISET_16") (pintype "bidirectional"))
    )
    (net (code "107") (name "Net-(U7-DRAIN)") (class "Default")
      (node (ref "C34") (pin "2") (pinfunction "2_2") (pintype "passive"))
      (node (ref "C35") (pin "2") (pinfunction "2_2") (pintype "passive"))
      (node (ref "R24") (pin "1") (pinfunction "1_1") (pintype "passive"))
      (node (ref "U7") (pin "3") (pinfunction "DRAIN_3") (pintype "bidirectional"))
      (node (ref "U8") (pin "1") (pinfunction "GATE_1") (pintype "bidirectional"))
    )
    (net (code "108") (name "Net-(U7-GATE)") (class "Default")
      (node (ref "C36") (pin "2") (pinfunction "2_2") (pintype "passive"))
      (node (ref "R27") (pin "2") (pinfunction "2_2") (pintype "passive"))
      (node (ref "U7") (pin "1") (pinfunction "GATE_1") (pintype "bidirectional"))
    )
    (net (code "109") (name "Net-(U21-DRAIN)") (class "Default")
      (node (ref "R37") (pin "1") (pinfunction "1_1") (pintype "passive"))
      (node (ref "U21") (pin "3") (pinfunction "DRAIN_3") (pintype "bidirectional"))
    )
    (net (code "110") (name "unconnected-(J1-ID-Pad4)") (class "Default")
      (node (ref "J1") (pin "4") (pinfunction "ID_4") (pintype "bidirectional"))
    )
    (net (code "111") (name "unconnected-(LCD1-BK_V-Pad15)") (class "Default")
      (node (ref "LCD1") (pin "15") (pinfunction "BK_V_15") (pintype "bidirectional"))
    )
    (net (code "112") (name "unconnected-(LCD1-D0-Pad7)") (class "Default")
      (node (ref "LCD1") (pin "7") (pinfunction "D0_7") (pintype "bidirectional"))
    )
    (net (code "113") (name "unconnected-(LCD1-D1-Pad8)") (class "Default")
      (node (ref "LCD1") (pin "8") (pinfunction "D1_8") (pintype "bidirectional"))
    )
    (net (code "114") (name "unconnected-(LCD1-D2-Pad9)") (class "Default")
      (node (ref "LCD1") (pin "9") (pinfunction "D2_9") (pintype "bidirectional"))
    )
    (net (code "115") (name "unconnected-(LCD1-D3-Pad10)") (class "Default")
      (node (ref "LCD1") (pin "10") (pinfunction "D3_10") (pintype "bidirectional"))
    )
    (net (code "116") (name "unconnected-(LCD1-D4-Pad11)") (class "Default")
      (node (ref "LCD1") (pin "11") (pinfunction "D4_11") (pintype "bidirectional"))
    )
    (net (code "117") (name "unconnected-(LCD1-E-Pad6)") (class "Default")
      (node (ref "LCD1") (pin "6") (pinfunction "E_6") (pintype "bidirectional"))
    )
    (net (code "118") (name "unconnected-(LCD1-RS-Pad4)") (class "Default")
      (node (ref "LCD1") (pin "4") (pinfunction "RS_4") (pintype "bidirectional"))
    )
    (net (code "119") (name "unconnected-(LCD1-R{slash}W-Pad5)") (class "Default")
      (node (ref "LCD1") (pin "5") (pinfunction "R/W_5") (pintype "bidirectional"))
    )
    (net (code "120") (name "unconnected-(LCD1-VLC-Pad3)") (class "Default")
      (node (ref "LCD1") (pin "3") (pinfunction "VLC_3") (pintype "bidirectional"))
    )
    (net (code "121") (name "unconnected-(U4-CTS#-Pad4)") (class "Default")
      (node (ref "U4") (pin "4") (pinfunction "CTS#_4") (pintype "bidirectional"))
    )
    (net (code "122") (name "unconnected-(U5-TMR-Pad14)") (class "Default")
      (node (ref "U5") (pin "14") (pinfunction "TMR_14") (pintype "bidirectional"))
    )
    (net (code "123") (name "unconnected-(U10-FT{slash}OUT-Pad7)") (class "Default")
      (node (ref "U10") (pin "7") (pinfunction "FT/OUT_7") (pintype "bidirectional"))
    )
    (net (code "124") (name "unconnected-(U13-ALT-PadP$3)") (class "Default")
      (node (ref "U13") (pin "P$3") (pinfunction "ALT_P$3") (pintype "bidirectional"))
    )
    (net (code "125") (name "unconnected-(U14-ALT-PadP$3)") (class "Default")
      (node (ref "U14") (pin "P$3") (pinfunction "ALT_P$3") (pintype "bidirectional"))
    )
    (net (code "126") (name "unconnected-(U15-ALT-PadP$3)") (class "Default")
      (node (ref "U15") (pin "P$3") (pinfunction "ALT_P$3") (pintype "bidirectional"))
    )
    (net (code "127") (name "unconnected-(U16-ALT-PadP$3)") (class "Default")
      (node (ref "U16") (pin "P$3") (pinfunction "ALT_P$3") (pintype "bidirectional"))
    )
    (net (code "128") (name "unconnected-(U17-ALT-PadP$3)") (class "Default")
      (node (ref "U17") (pin "P$3") (pinfunction "ALT_P$3") (pintype "bidirectional"))
    )
    (net (code "129") (name "unconnected-(U18-ALT-PadP$3)") (class "Default")
      (node (ref "U18") (pin "P$3") (pinfunction "ALT_P$3") (pintype "bidirectional"))
    )
    (net (code "130") (name "unconnected-(U19-ALT-PadP$3)") (class "Default")
      (node (ref "U19") (pin "P$3") (pinfunction "ALT_P$3") (pintype "bidirectional"))
    )
    (net (code "131") (name "unconnected-(U20-ALT-PadP$3)") (class "Default")
      (node (ref "U20") (pin "P$3") (pinfunction "ALT_P$3") (pintype "bidirectional"))
    )
  )
)
